# STM32H730_PINOUT.net
KiCad netlist of a schematic drawn in Altium Designer
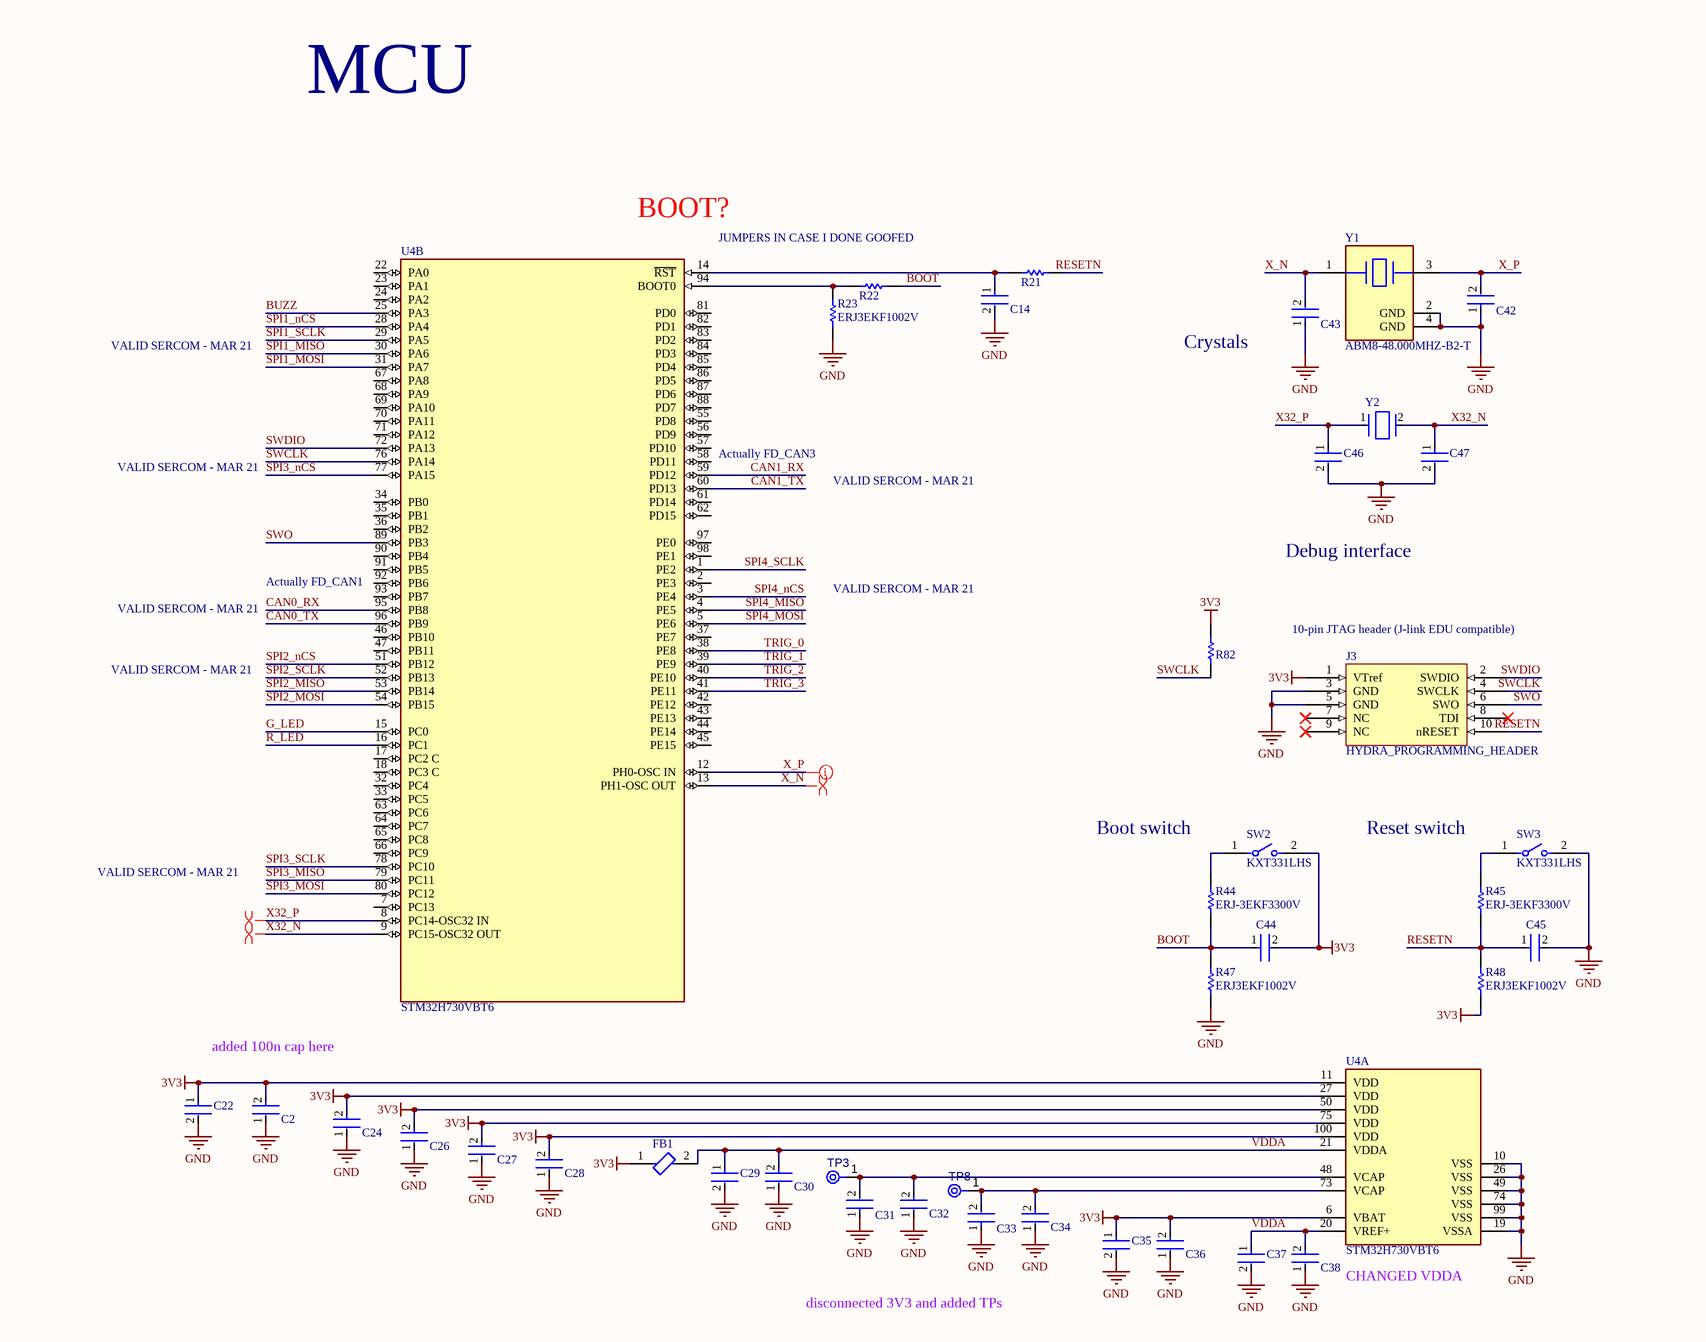
[diagram p0: STM32H730_PINOUT.SchDoc, top left]
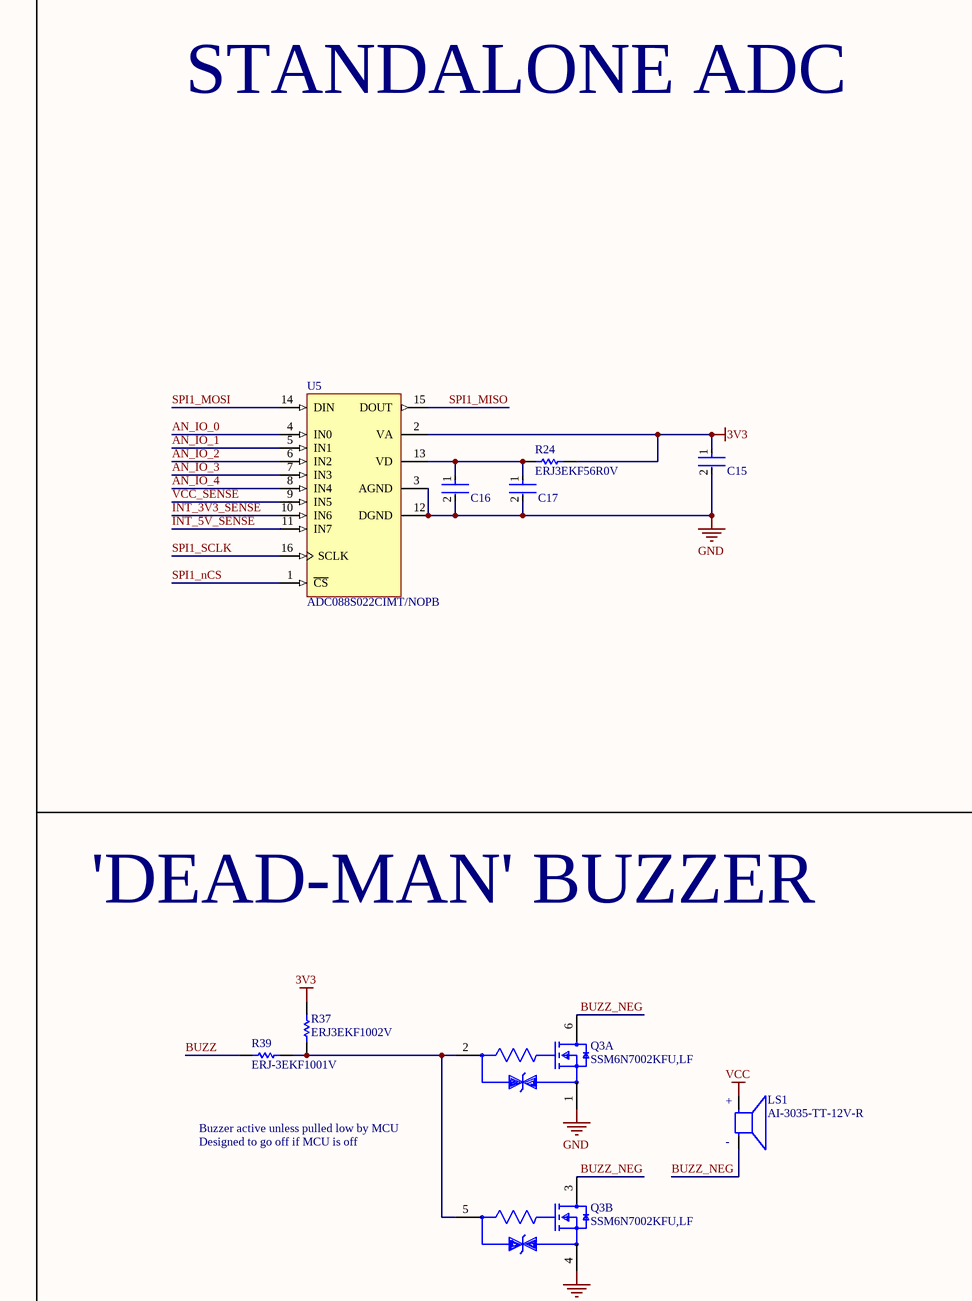
[diagram p1: STM32H730_PINOUT.SchDoc, top middle]
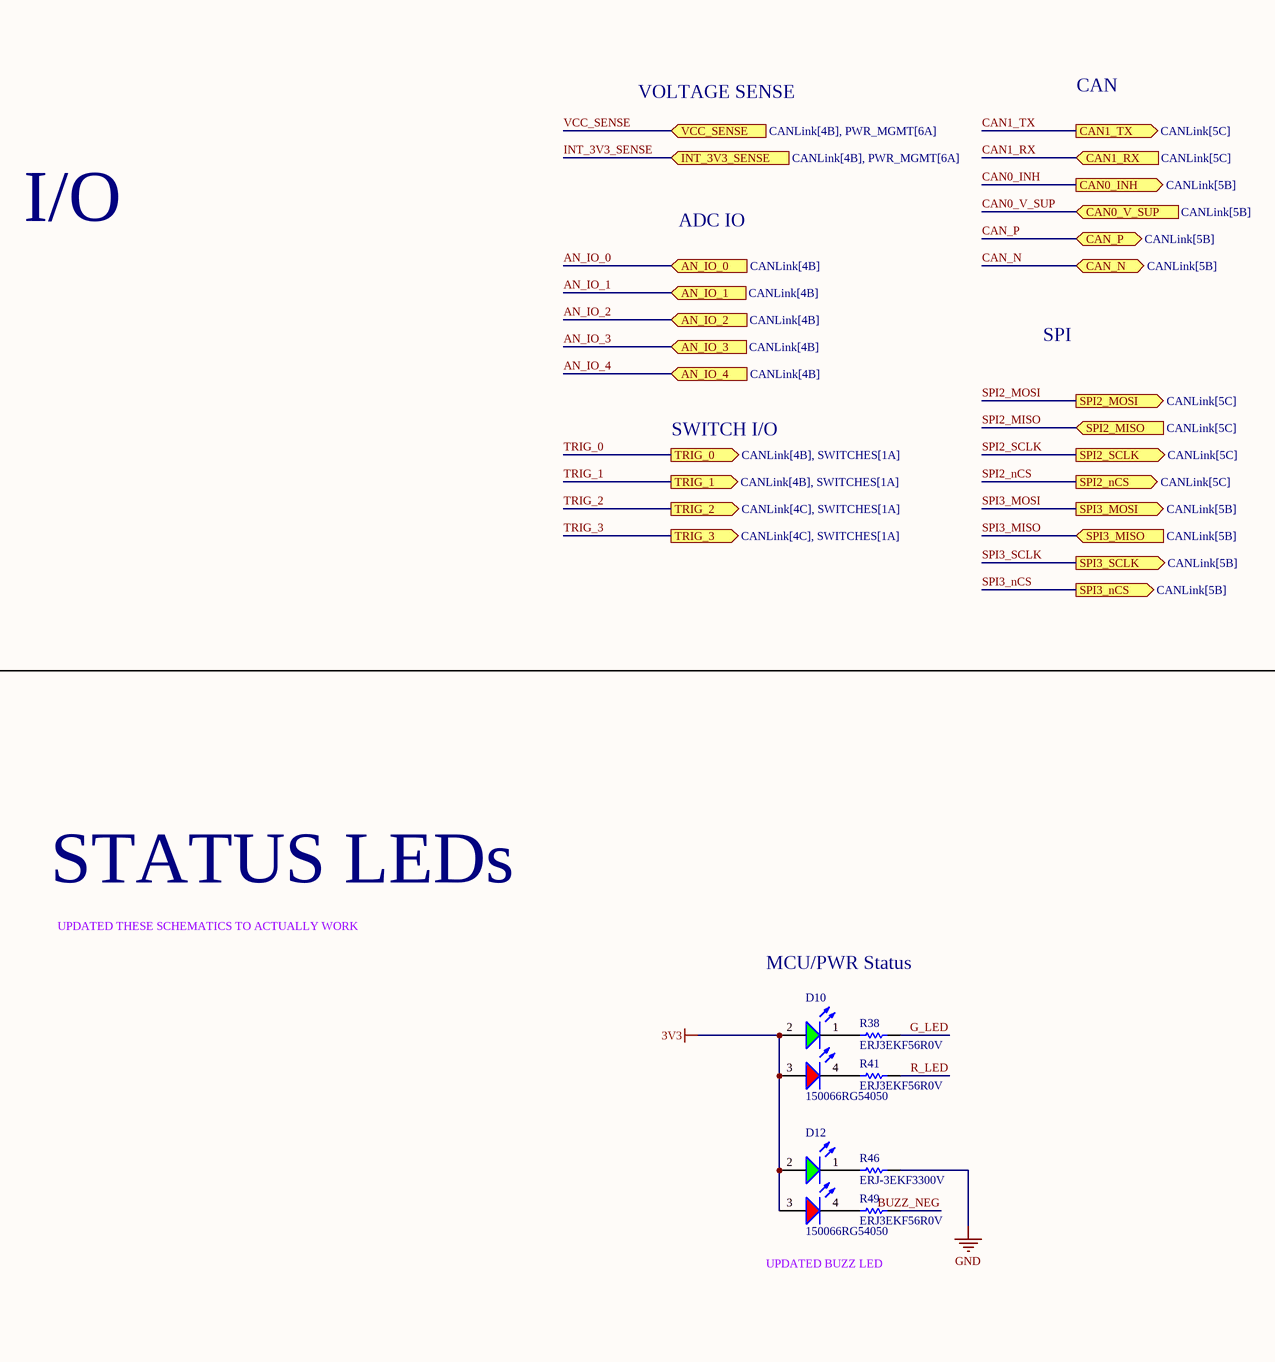
[diagram p2: STM32H730_PINOUT.SchDoc, top right]
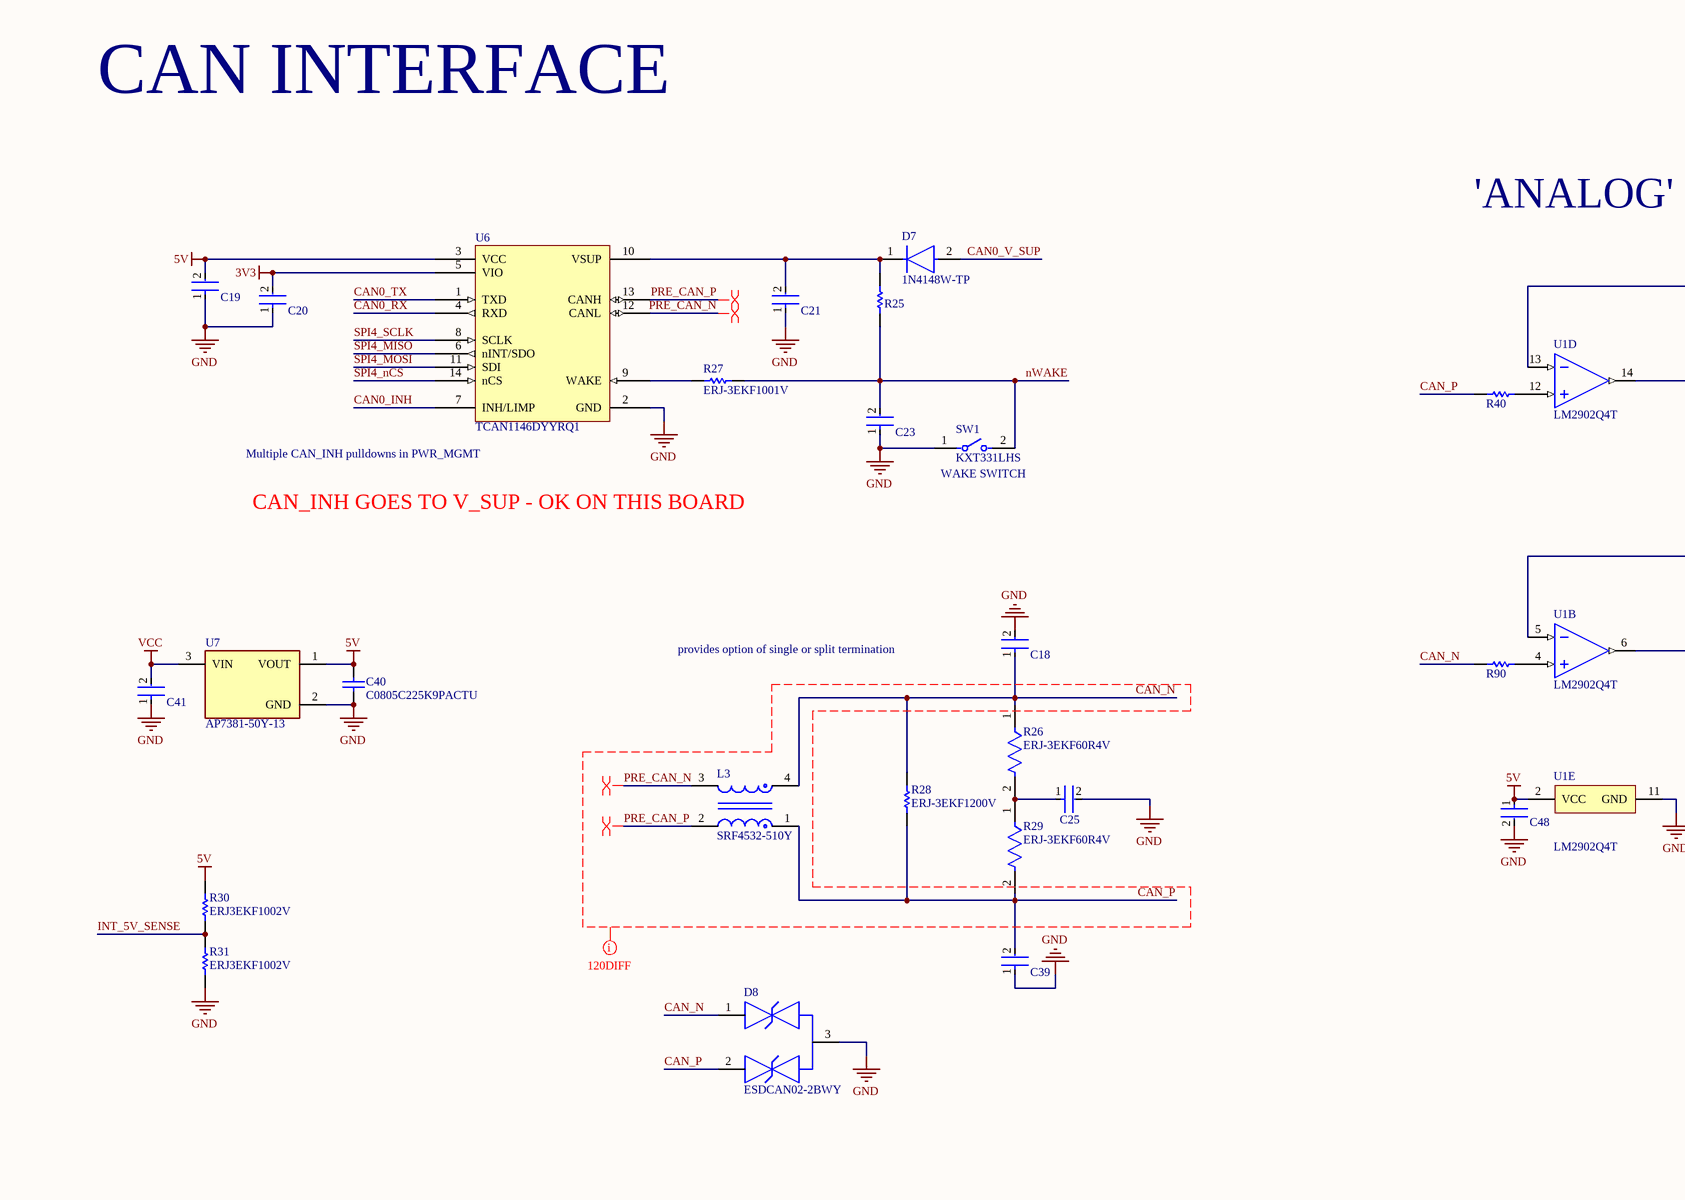
[diagram p3: STM32H730_PINOUT.SchDoc, bottom left]
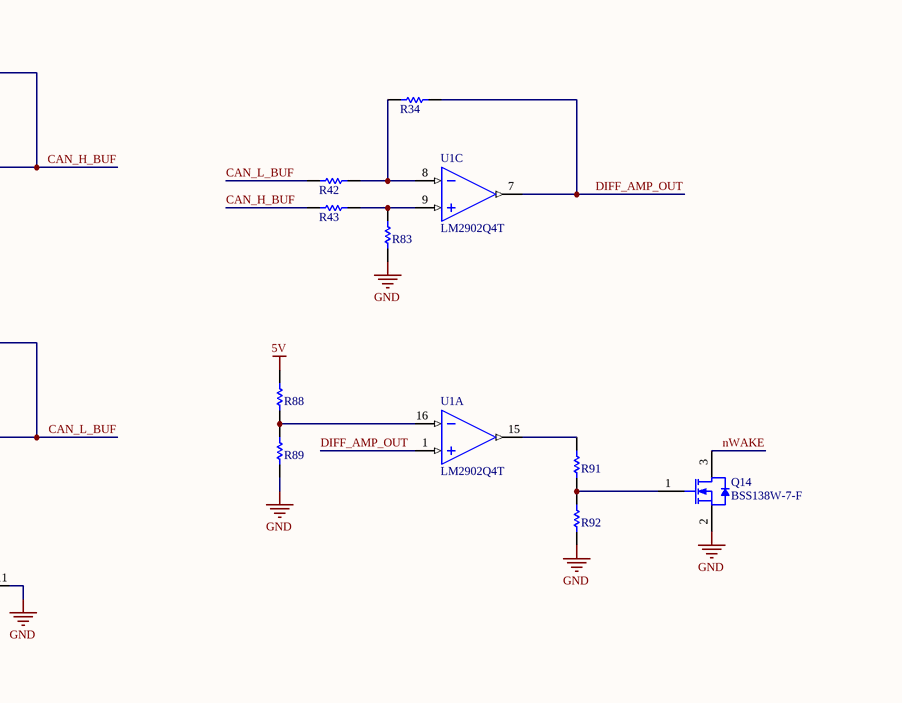
[diagram p4: STM32H730_PINOUT.SchDoc, bottom middle]
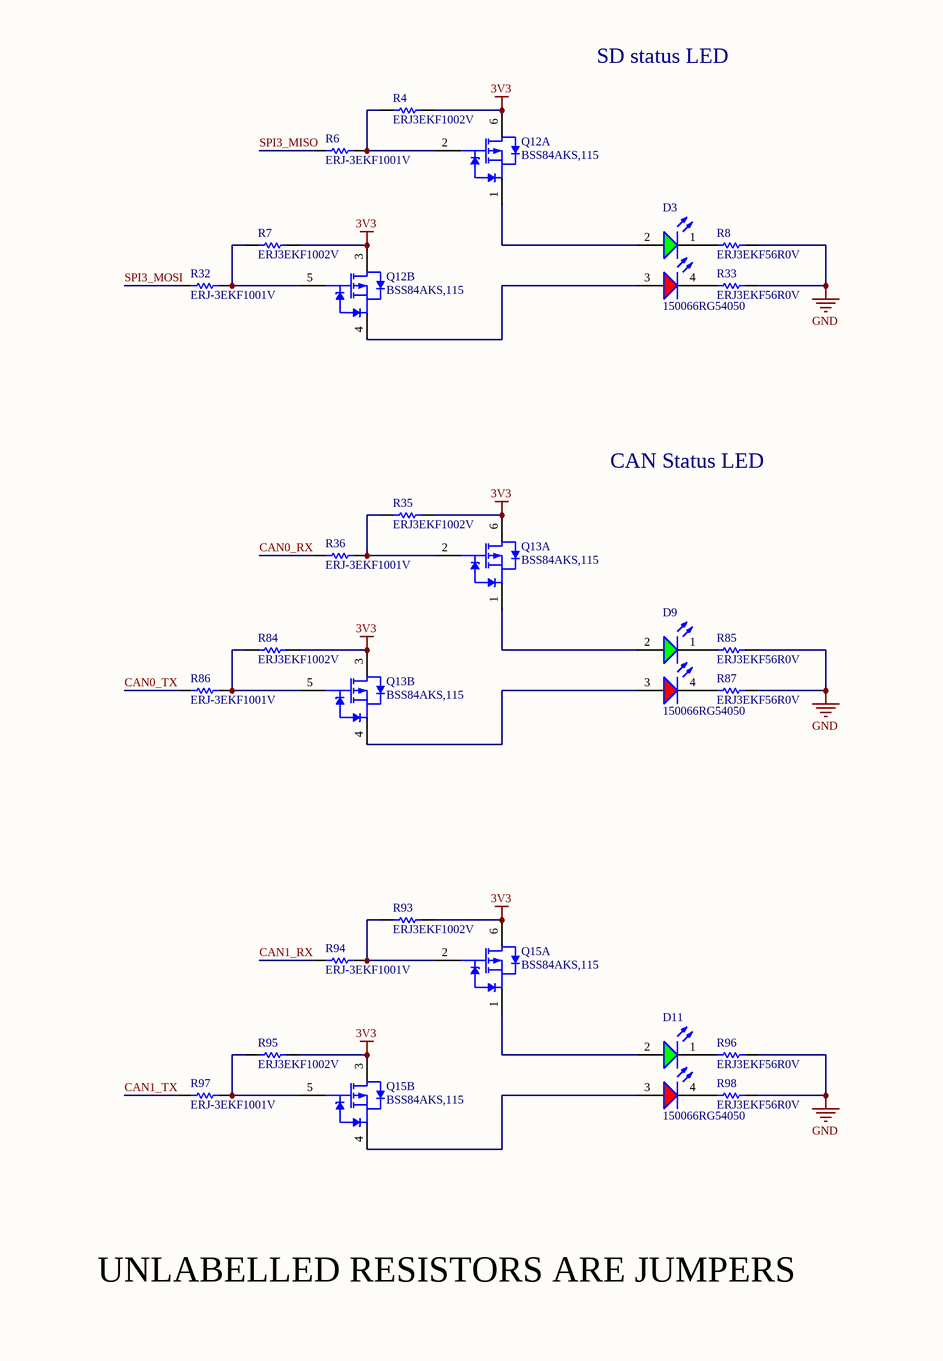
[diagram p5: STM32H730_PINOUT.SchDoc, bottom right]

(export (version "E")
  (design (tool "Eeschema 10.0.6"))
  (components
    (comp (ref "C2")
      (value "GRM155R71C104KA88D")
      (footprint "FP-GRM15-MFG")
      (description "CAP CER 0.1UF 16V X7R 0402")
      (fields
        (field (name "TOLERANCE") "10%")
        (field (name "OCTOPART") "https://octopart.com/grm155r71c104ka88d-murata-196880")
      )
      (libsource (lib "Altium Content Vault") (part "236180d848d6139a670b325ea6854c9"))
    )
    (comp (ref "C14")
      (value "C0402C104K8PACTU")
      (footprint "FP-C0402-BB-MFG")
      (description "CAP CER 0.1UF 10V X5R 0402")
      (fields (field (name "MANUFACTURER") "Kemet") (field (name "TOLERANCE") "0.1"))
      (libsource (lib "Altium Content Vault") (part "b4654b650e69147ec39a6b967a45e02"))
    )
    (comp (ref "C15")
      (value "C0402C104K8PACTU")
      (footprint "FP-C0402-BB-MFG")
      (description "CAP CER 0.1UF 10V X5R 0402")
      (fields (field (name "MANUFACTURER") "Kemet") (field (name "TOLERANCE") "0.1"))
      (libsource (lib "Altium Content Vault") (part "b4654b650e69147ec39a6b967a45e02"))
    )
    (comp (ref "C16")
      (value "C0402C104K8PACTU")
      (footprint "FP-C0402-BB-MFG")
      (description "CAP CER 0.1UF 10V X5R 0402")
      (fields (field (name "MANUFACTURER") "Kemet") (field (name "TOLERANCE") "0.1"))
      (libsource (lib "Altium Content Vault") (part "b4654b650e69147ec39a6b967a45e02"))
    )
    (comp (ref "C17")
      (value "C0402C104K8PACTU")
      (footprint "FP-C0402-BB-MFG")
      (description "CAP CER 0.1UF 10V X5R 0402")
      (fields (field (name "MANUFACTURER") "Kemet") (field (name "TOLERANCE") "0.1"))
      (libsource (lib "Altium Content Vault") (part "b4654b650e69147ec39a6b967a45e02"))
    )
    (comp (ref "C18")
      (value "C0402C104K8PACTU")
      (footprint "FP-C0402-BB-MFG")
      (description "CAP CER 0.1UF 10V X5R 0402")
      (fields (field (name "MANUFACTURER") "Kemet") (field (name "TOLERANCE") "0.1"))
      (libsource (lib "Altium Content Vault") (part "b4654b650e69147ec39a6b967a45e02"))
    )
    (comp (ref "C19")
      (value "C0402C104K8PACTU")
      (footprint "FP-C0402-BB-MFG")
      (description "CAP CER 0.1UF 10V X5R 0402")
      (fields (field (name "MANUFACTURER") "Kemet") (field (name "TOLERANCE") "0.1"))
      (libsource (lib "Altium Content Vault") (part "b4654b650e69147ec39a6b967a45e02"))
    )
    (comp (ref "C20")
      (value "C0402C104K8PACTU")
      (footprint "FP-C0402-BB-MFG")
      (description "CAP CER 0.1UF 10V X5R 0402")
      (fields (field (name "MANUFACTURER") "Kemet") (field (name "TOLERANCE") "0.1"))
      (libsource (lib "Altium Content Vault") (part "b4654b650e69147ec39a6b967a45e02"))
    )
    (comp (ref "C21")
      (value "C0402C104K8PACTU")
      (footprint "FP-C0402-BB-MFG")
      (description "CAP CER 0.1UF 10V X5R 0402")
      (fields (field (name "MANUFACTURER") "Kemet") (field (name "TOLERANCE") "0.1"))
      (libsource (lib "Altium Content Vault") (part "b4654b650e69147ec39a6b967a45e02"))
    )
    (comp (ref "C22")
      (value "C1005X5R1A475K050BC")
      (footprint "FP-C1005-050-0_15-MFG")
      (description "CAP CER 4.7UF 10V X5R 0402")
      (fields (field (name "TOLERANCE") "10%"))
      (libsource (lib "Altium Content Vault") (part "b4654b650e69147ec39a6b967a45e02"))
    )
    (comp (ref "C23")
      (value "C0402C104K8PACTU")
      (footprint "FP-C0402-BB-MFG")
      (description "CAP CER 0.1UF 10V X5R 0402")
      (fields (field (name "MANUFACTURER") "Kemet") (field (name "TOLERANCE") "0.1"))
      (libsource (lib "Altium Content Vault") (part "b4654b650e69147ec39a6b967a45e02"))
    )
    (comp (ref "C24")
      (value "GRM155R71C104KA88D")
      (footprint "FP-GRM15-MFG")
      (description "CAP CER 0.1UF 16V X7R 0402")
      (fields
        (field (name "TOLERANCE") "10%")
        (field (name "OCTOPART") "https://octopart.com/grm155r71c104ka88d-murata-196880")
      )
      (libsource (lib "Altium Content Vault") (part "236180d848d6139a670b325ea6854c9"))
    )
    (comp (ref "C25")
      (value "C0402C104K8PACTU")
      (footprint "FP-C0402-BB-MFG")
      (description "CAP CER 0.1UF 10V X5R 0402")
      (fields (field (name "MANUFACTURER") "Kemet") (field (name "TOLERANCE") "0.1"))
      (libsource (lib "Altium Content Vault") (part "b4654b650e69147ec39a6b967a45e02"))
    )
    (comp (ref "C26")
      (value "GRM155R71C104KA88D")
      (footprint "FP-GRM15-MFG")
      (description "CAP CER 0.1UF 16V X7R 0402")
      (fields
        (field (name "TOLERANCE") "10%")
        (field (name "OCTOPART") "https://octopart.com/grm155r71c104ka88d-murata-196880")
      )
      (libsource (lib "Altium Content Vault") (part "236180d848d6139a670b325ea6854c9"))
    )
    (comp (ref "C27")
      (value "GRM155R71C104KA88D")
      (footprint "FP-GRM15-MFG")
      (description "CAP CER 0.1UF 16V X7R 0402")
      (fields
        (field (name "TOLERANCE") "10%")
        (field (name "OCTOPART") "https://octopart.com/grm155r71c104ka88d-murata-196880")
      )
      (libsource (lib "Altium Content Vault") (part "236180d848d6139a670b325ea6854c9"))
    )
    (comp (ref "C28")
      (value "GRM155R71C104KA88D")
      (footprint "FP-GRM15-MFG")
      (description "CAP CER 0.1UF 16V X7R 0402")
      (fields
        (field (name "TOLERANCE") "10%")
        (field (name "OCTOPART") "https://octopart.com/grm155r71c104ka88d-murata-196880")
      )
      (libsource (lib "Altium Content Vault") (part "236180d848d6139a670b325ea6854c9"))
    )
    (comp (ref "C29")
      (value "EMK105BJ105KV-F")
      (footprint "FP-0402-L_1_0_0_05-W_0_5-IPC_A")
      (description "None")
      (fields (field (name "TOLERANCE") "10%"))
      (libsource (lib "Altium Content Vault") (part "b4654b650e69147ec39a6b967a45e02"))
    )
    (comp (ref "C30")
      (value "GRM155R71C104KA88D")
      (footprint "FP-GRM15-MFG")
      (description "CAP CER 0.1UF 16V X7R 0402")
      (fields
        (field (name "TOLERANCE") "10%")
        (field (name "OCTOPART") "https://octopart.com/grm155r71c104ka88d-murata-196880")
      )
      (libsource (lib "Altium Content Vault") (part "236180d848d6139a670b325ea6854c9"))
    )
    (comp (ref "C31")
      (value "C1005X7S1A225K050BC")
      (footprint "FP-C1005-050-0_15-0_1-MFG")
      (description "CAP CER 2.2UF 10V X7S 0402")
      (fields (field (name "TOLERANCE") "10%"))
      (libsource (lib "Altium Content Vault") (part "b4654b650e69147ec39a6b967a45e02"))
    )
    (comp (ref "C32")
      (value "GRM155R71C104KA88D")
      (footprint "FP-GRM15-MFG")
      (description "CAP CER 0.1UF 16V X7R 0402")
      (fields
        (field (name "TOLERANCE") "10%")
        (field (name "OCTOPART") "https://octopart.com/grm155r71c104ka88d-murata-196880")
      )
      (libsource (lib "Altium Content Vault") (part "236180d848d6139a670b325ea6854c9"))
    )
    (comp (ref "C33")
      (value "C1005X7S1A225K050BC")
      (footprint "FP-C1005-050-0_15-0_1-MFG")
      (description "CAP CER 2.2UF 10V X7S 0402")
      (fields (field (name "TOLERANCE") "10%"))
      (libsource (lib "Altium Content Vault") (part "b4654b650e69147ec39a6b967a45e02"))
    )
    (comp (ref "C34")
      (value "GRM155R71C104KA88D")
      (footprint "FP-GRM15-MFG")
      (description "CAP CER 0.1UF 16V X7R 0402")
      (fields
        (field (name "TOLERANCE") "10%")
        (field (name "OCTOPART") "https://octopart.com/grm155r71c104ka88d-murata-196880")
      )
      (libsource (lib "Altium Content Vault") (part "236180d848d6139a670b325ea6854c9"))
    )
    (comp (ref "C35")
      (value "EMK105BJ105KV-F")
      (footprint "FP-0402-L_1_0_0_05-W_0_5-IPC_A")
      (description "None")
      (fields (field (name "TOLERANCE") "10%"))
      (libsource (lib "Altium Content Vault") (part "b4654b650e69147ec39a6b967a45e02"))
    )
    (comp (ref "C36")
      (value "GRM155R71C104KA88D")
      (footprint "FP-GRM15-MFG")
      (description "CAP CER 0.1UF 16V X7R 0402")
      (fields
        (field (name "TOLERANCE") "10%")
        (field (name "OCTOPART") "https://octopart.com/grm155r71c104ka88d-murata-196880")
      )
      (libsource (lib "Altium Content Vault") (part "236180d848d6139a670b325ea6854c9"))
    )
    (comp (ref "C37")
      (value "EMK105BJ105KV-F")
      (footprint "FP-0402-L_1_0_0_05-W_0_5-IPC_A")
      (description "None")
      (fields (field (name "TOLERANCE") "10%"))
      (libsource (lib "Altium Content Vault") (part "b4654b650e69147ec39a6b967a45e02"))
    )
    (comp (ref "C38")
      (value "GRM155R71C104KA88D")
      (footprint "FP-GRM15-MFG")
      (description "CAP CER 0.1UF 16V X7R 0402")
      (fields
        (field (name "TOLERANCE") "10%")
        (field (name "OCTOPART") "https://octopart.com/grm155r71c104ka88d-murata-196880")
      )
      (libsource (lib "Altium Content Vault") (part "236180d848d6139a670b325ea6854c9"))
    )
    (comp (ref "C39")
      (value "C0402C104K8PACTU")
      (footprint "FP-C0402-BB-MFG")
      (description "CAP CER 0.1UF 10V X5R 0402")
      (fields (field (name "MANUFACTURER") "Kemet") (field (name "TOLERANCE") "0.1"))
      (libsource (lib "Altium Content Vault") (part "b4654b650e69147ec39a6b967a45e02"))
    )
    (comp (ref "C40")
      (value "C0805C225K9PACTU")
      (footprint "CAPC2013X145X50ML20T25")
      (fields (field (name "MANUFACTURER") "Kemet"))
      (libsource (lib "Altium Content Vault") (part "CAP"))
    )
    (comp (ref "C41")
      (value "C0402C104K8PACTU")
      (footprint "FP-C0402-BB-MFG")
      (description "CAP CER 0.1UF 10V X5R 0402")
      (fields (field (name "MANUFACTURER") "Kemet") (field (name "TOLERANCE") "0.1"))
      (libsource (lib "Altium Content Vault") (part "b4654b650e69147ec39a6b967a45e02"))
    )
    (comp (ref "C42")
      (value "08051A6R8CAT2A")
      (footprint "FP-0805-L_2_01_0_2-W_1_25-MFG")
      (description "General Purpose Ceramic Capacitor, 0805, 6.8pF, 0.25pF, C0G, 30ppm/°C, 100V")
      (fields (field (name "VOLTAGE") "100V") (field (name "TOLERANCE") "5%"))
      (libsource (lib "Altium Content Vault") (part "02cd4be3c70576c341d710602a673aa"))
    )
    (comp (ref "C43")
      (value "08051A6R8CAT2A")
      (footprint "FP-0805-L_2_01_0_2-W_1_25-MFG")
      (description "General Purpose Ceramic Capacitor, 0805, 6.8pF, 0.25pF, C0G, 30ppm/°C, 100V")
      (fields (field (name "VOLTAGE") "100V") (field (name "TOLERANCE") "5%"))
      (libsource (lib "Altium Content Vault") (part "02cd4be3c70576c341d710602a673aa"))
    )
    (comp (ref "C44")
      (value "C0402C104K8PACTU")
      (footprint "FP-C0402-BB-MFG")
      (description "CAP CER 0.1UF 10V X5R 0402")
      (fields (field (name "MANUFACTURER") "Kemet") (field (name "TOLERANCE") "0.1"))
      (libsource (lib "Altium Content Vault") (part "b4654b650e69147ec39a6b967a45e02"))
    )
    (comp (ref "C45")
      (value "C0402C104K8PACTU")
      (footprint "FP-C0402-BB-MFG")
      (description "CAP CER 0.1UF 10V X5R 0402")
      (fields (field (name "MANUFACTURER") "Kemet") (field (name "TOLERANCE") "0.1"))
      (libsource (lib "Altium Content Vault") (part "b4654b650e69147ec39a6b967a45e02"))
    )
    (comp (ref "C46")
      (value "C0805C180J5GACTU")
      (footprint "FP-C0805C-DN-MFG")
      (description "CAP CER 18PF 50V C0G/NP0 0805")
      (fields
        (field (name "OCTOPART") "https://octopart.com/c0805c180j5gactu-kemet-144810")
        (field (name "TOLERANCE") "0.05")
      )
      (libsource (lib "Altium Content Vault") (part "b4654b650e69147ec39a6b967a45e02"))
    )
    (comp (ref "C47")
      (value "C0805C180J5GACTU")
      (footprint "FP-C0805C-DN-MFG")
      (description "CAP CER 18PF 50V C0G/NP0 0805")
      (fields
        (field (name "OCTOPART") "https://octopart.com/c0805c180j5gactu-kemet-144810")
        (field (name "TOLERANCE") "0.05")
      )
      (libsource (lib "Altium Content Vault") (part "b4654b650e69147ec39a6b967a45e02"))
    )
    (comp (ref "C48")
      (value "C0402C104K8PACTU")
      (footprint "FP-C0402-BB-MFG")
      (description "CAP CER 0.1UF 10V X5R 0402")
      (fields (field (name "MANUFACTURER") "Kemet") (field (name "TOLERANCE") "0.1"))
      (libsource (lib "Altium Content Vault") (part "b4654b650e69147ec39a6b967a45e02"))
    )
    (comp (ref "D3")
      (value "150066RG54050")
      (footprint "WL-SBCD_0606")
      (description "Led, Red/Grn, 180Mcd/230Mcd, 624Nm/525Nm Rohs Compliant: Yes")
      (libsource (lib "uORocketry Hardware") (part "WL-SBCD_0606_Red & Green"))
    )
    (comp (ref "D7")
      (value "1N4148W-TP")
      (footprint "FP-SOD-123-IPC_A")
      (description "DIODE GEN PURP 100V 150MA SOD123")
      (libsource (lib "Altium Content Vault") (part "d7152d700b627762746794eb795d46e"))
    )
    (comp (ref "D8")
      (value "ESDCAN02-2BWY")
      (footprint "FP-SOT323-3L-MFG")
      (description "TVS DIODE 26.5V 44V SOT323-3")
      (fields
        (field (name "MANUFACTURER") "STMicroelectronics")
        (field (name "OCTOPART") "https://octopart.com/esdcan02-2bwy-stmicroelectronics-58631133")
      )
      (libsource (lib "Altium Content Vault") (part "0b9019fb5e52ed66df21ec1535be59d"))
    )
    (comp (ref "D9")
      (value "150066RG54050")
      (footprint "WL-SBCD_0606")
      (description "Led, Red/Grn, 180Mcd/230Mcd, 624Nm/525Nm Rohs Compliant: Yes")
      (libsource (lib "uORocketry Hardware") (part "WL-SBCD_0606_Red & Green"))
    )
    (comp (ref "D10")
      (value "150066RG54050")
      (footprint "WL-SBCD_0606")
      (description "Led, Red/Grn, 180Mcd/230Mcd, 624Nm/525Nm Rohs Compliant: Yes")
      (libsource (lib "uORocketry Hardware") (part "WL-SBCD_0606_Red & Green"))
    )
    (comp (ref "D11")
      (value "150066RG54050")
      (footprint "WL-SBCD_0606")
      (description "Led, Red/Grn, 180Mcd/230Mcd, 624Nm/525Nm Rohs Compliant: Yes")
      (libsource (lib "uORocketry Hardware") (part "WL-SBCD_0606_Red & Green"))
    )
    (comp (ref "D12")
      (value "150066RG54050")
      (footprint "WL-SBCD_0606")
      (description "Led, Red/Grn, 180Mcd/230Mcd, 624Nm/525Nm Rohs Compliant: Yes")
      (libsource (lib "uORocketry Hardware") (part "WL-SBCD_0606_Red & Green"))
    )
    (comp (ref "FB1")
      (value "BLM15PX601SN1D")
      (footprint "FP-BLM15-0_05-MFG")
      (description "Chip Ferrite Bead, 0402, 600Ω @ 100MHz, 0.23Ω, 25%, 900mA")
      (fields (field (name "TOLERANCE") "25%"))
      (libsource (lib "Altium Content Vault") (part "5f30dd21d616792df468990f7003faa"))
    )
    (comp (ref "J3")
      (value "HYDRA_PROGRAMMING_HEADER")
      (footprint "3220-10-0300-00-Footprint-1")
      (description "CONN HEADER SMD 10POS 1.27MM (specifically compatible with J-Link EDU cable) PN: 3220-10-0300-00")
      (libsource (lib "uORocketry Hardware") (part "3220-10-0300-00-Symbol-1"))
    )
    (comp (ref "L3")
      (value "SRF4532-510Y")
      (footprint "FP-SRF4532-MFG")
      (description "CMC 51UH 200MA 2LN 2KOHM SMD")
      (fields (field (name "TOLERANCE") "50%"))
      (libsource (lib "Altium Content Vault") (part "aca3f6a10b859f211cca95010157f3b"))
    )
    (comp (ref "LS1")
      (value "AI-3035-TT-12V-R")
      (footprint "AI-3035-TT-12V-R-Footprint-1")
      (description "Audio Indicator 12V 12mA 110dBA 3.5KHz Resonant Frequency Thru-Hole")
      (libsource (lib "uORocketry Hardware") (part "AI-3035-TT-12V-R"))
    )
    (comp (ref "Q3")
      (value "SSM6N7002KFU,LF")
      (footprint "FP-SSOP6-P-0_65A-MFG")
      (description "MOSFET 2N-CH 60V 0.3A")
      (libsource (lib "Altium Content Vault") (part "088aa6ac103fdeebe0d1c52ece6b7b9"))
    )
    (comp (ref "Q12")
      (value "BSS84AKS,115")
      (footprint "NXP-SOT363_L")
      (description "Dual P-Channel Trench MOSFET, -50 V, -0.16 A, -55 to 150 degC, 6-Pin SOT363, Tape and Reel")
      (fields (field (name "MANUFACTURER") "NXP Semiconductors"))
      (libsource (lib "Altium Content Vault") (part "NXP-PPMOS-SGDSGD-6_A"))
    )
    (comp (ref "Q13")
      (value "BSS84AKS,115")
      (footprint "NXP-SOT363_L")
      (description "Dual P-Channel Trench MOSFET, -50 V, -0.16 A, -55 to 150 degC, 6-Pin SOT363, Tape and Reel")
      (fields (field (name "MANUFACTURER") "NXP Semiconductors"))
      (libsource (lib "Altium Content Vault") (part "NXP-PPMOS-SGDSGD-6_A"))
    )
    (comp (ref "Q14")
      (value "BSS138W-7-F")
      (footprint "DIOD-SOT323-3_V")
      (fields (field (name "MANUFACTURER") "DiodesIncorporated"))
      (libsource (lib "Altium Content Vault") (part "NEMOS-GSD-3"))
    )
    (comp (ref "Q15")
      (value "BSS84AKS,115")
      (footprint "NXP-SOT363_L")
      (description "Dual P-Channel Trench MOSFET, -50 V, -0.16 A, -55 to 150 degC, 6-Pin SOT363, Tape and Reel")
      (fields (field (name "MANUFACTURER") "NXP Semiconductors"))
      (libsource (lib "Altium Content Vault") (part "NXP-PPMOS-SGDSGD-6_A"))
    )
    (comp (ref "R4")
      (value "ERJ3EKF1002V")
      (footprint "RESC1609X55X30LL15T15")
      (description "Chip Resistor, 10 KOhm, +/- 1%, 0.1 W, -55 to 155 degC, 0603 (1608 Metric), RoHS, Tape and Reel")
      (fields (field (name "TOLERANCE") "1%") (field (name "MANUFACTURER") "Panasonic"))
      (libsource (lib "Altium Content Vault") (part "RES-2"))
    )
    (comp (ref "R6")
      (value "ERJ-3EKF1001V")
      (footprint "RESC1608X55X30LL15T15")
      (fields (field (name "MANUFACTURER") "Panasonic"))
      (libsource (lib "Altium Content Vault") (part "RES"))
    )
    (comp (ref "R7")
      (value "ERJ3EKF1002V")
      (footprint "RESC1609X55X30LL15T15")
      (description "Chip Resistor, 10 KOhm, +/- 1%, 0.1 W, -55 to 155 degC, 0603 (1608 Metric), RoHS, Tape and Reel")
      (fields (field (name "TOLERANCE") "1%") (field (name "MANUFACTURER") "Panasonic"))
      (libsource (lib "Altium Content Vault") (part "RES-2"))
    )
    (comp (ref "R8")
      (value "ERJ3EKF56R0V")
      (footprint "RESC1608X55X30NL15T15")
      (fields (field (name "MANUFACTURER") "Panasonic"))
      (libsource (lib "Altium Content Vault") (part "RES"))
    )
    (comp (ref "R21")
      (value "0402 JUMPER 0 OHM")
      (footprint "RESC1005X40X25NL05T05")
      (description "READ THE NAME")
      (libsource (lib "uORocketry Hardware") (part "RES"))
    )
    (comp (ref "R22")
      (value "0402 JUMPER 0 OHM")
      (footprint "RESC1005X40X25NL05T05")
      (description "READ THE NAME")
      (libsource (lib "uORocketry Hardware") (part "RES"))
    )
    (comp (ref "R23")
      (value "ERJ3EKF1002V")
      (footprint "RESC1609X55X30LL15T15")
      (description "Chip Resistor, 10 KOhm, +/- 1%, 0.1 W, -55 to 155 degC, 0603 (1608 Metric), RoHS, Tape and Reel")
      (fields (field (name "TOLERANCE") "1%") (field (name "MANUFACTURER") "Panasonic"))
      (libsource (lib "Altium Content Vault") (part "RES-2"))
    )
    (comp (ref "R24")
      (value "ERJ3EKF56R0V")
      (footprint "RESC1608X55X30NL15T15")
      (fields (field (name "MANUFACTURER") "Panasonic"))
      (libsource (lib "Altium Content Vault") (part "RES"))
    )
    (comp (ref "R25")
      (value "ERJ3EKF1002V")
      (footprint "RESC1609X55X30LL15T15")
      (description "Chip Resistor, 10 KOhm, +/- 1%, 0.1 W, -55 to 155 degC, 0603 (1608 Metric), RoHS, Tape and Reel")
      (fields (field (name "TOLERANCE") "1%") (field (name "MANUFACTURER") "Panasonic"))
      (libsource (lib "Altium Content Vault") (part "RES-2"))
    )
    (comp (ref "R26")
      (value "ERJ-3EKF60R4V")
      (footprint "FP-ERJ3EK-IPC_C")
      (description "RES SMD 60.4 OHM 1% 1/10W 0603")
      (fields (field (name "TOLERANCE") "1%"))
      (libsource (lib "Altium Content Vault") (part "1029c3af85768c4190bb7ad29bc67b5"))
    )
    (comp (ref "R27")
      (value "ERJ-3EKF1001V")
      (footprint "RESC1608X55X30LL15T15")
      (fields (field (name "MANUFACTURER") "Panasonic"))
      (libsource (lib "Altium Content Vault") (part "RES"))
    )
    (comp (ref "R28")
      (value "ERJ-3EKF1200V")
      (footprint "RESC1609X55X30ML15T15")
      (description "Chip Resistor, 120 Ohm, +/- 1%, 0.1 W, -55 to 155 degC, 0603 (1608 Metric), RoHS, Tape and Reel")
      (fields (field (name "TOLERANCE") "1%") (field (name "MANUFACTURER") "Panasonic"))
      (libsource (lib "Altium Content Vault") (part "RES-2"))
    )
    (comp (ref "R29")
      (value "ERJ-3EKF60R4V")
      (footprint "FP-ERJ3EK-IPC_C")
      (description "RES SMD 60.4 OHM 1% 1/10W 0603")
      (fields (field (name "TOLERANCE") "1%"))
      (libsource (lib "Altium Content Vault") (part "1029c3af85768c4190bb7ad29bc67b5"))
    )
    (comp (ref "R30")
      (value "ERJ3EKF1002V")
      (footprint "RESC1609X55X30LL15T15")
      (description "Chip Resistor, 10 KOhm, +/- 1%, 0.1 W, -55 to 155 degC, 0603 (1608 Metric), RoHS, Tape and Reel")
      (fields (field (name "TOLERANCE") "1%") (field (name "MANUFACTURER") "Panasonic"))
      (libsource (lib "Altium Content Vault") (part "RES-2"))
    )
    (comp (ref "R31")
      (value "ERJ3EKF1002V")
      (footprint "RESC1609X55X30LL15T15")
      (description "Chip Resistor, 10 KOhm, +/- 1%, 0.1 W, -55 to 155 degC, 0603 (1608 Metric), RoHS, Tape and Reel")
      (fields (field (name "TOLERANCE") "1%") (field (name "MANUFACTURER") "Panasonic"))
      (libsource (lib "Altium Content Vault") (part "RES-2"))
    )
    (comp (ref "R32")
      (value "ERJ-3EKF1001V")
      (footprint "RESC1608X55X30LL15T15")
      (fields (field (name "MANUFACTURER") "Panasonic"))
      (libsource (lib "Altium Content Vault") (part "RES"))
    )
    (comp (ref "R33")
      (value "ERJ3EKF56R0V")
      (footprint "RESC1608X55X30NL15T15")
      (fields (field (name "MANUFACTURER") "Panasonic"))
      (libsource (lib "Altium Content Vault") (part "RES"))
    )
    (comp (ref "R34")
      (value "ERJ3EKF1002V")
      (footprint "RESC1609X55X30LL15T15")
      (description "Chip Resistor, 10 KOhm, +/- 1%, 0.1 W, -55 to 155 degC, 0603 (1608 Metric), RoHS, Tape and Reel")
      (fields (field (name "TOLERANCE") "1%") (field (name "MANUFACTURER") "Panasonic"))
      (libsource (lib "Altium Content Vault") (part "RES-2"))
    )
    (comp (ref "R35")
      (value "ERJ3EKF1002V")
      (footprint "RESC1609X55X30LL15T15")
      (description "Chip Resistor, 10 KOhm, +/- 1%, 0.1 W, -55 to 155 degC, 0603 (1608 Metric), RoHS, Tape and Reel")
      (fields (field (name "TOLERANCE") "1%") (field (name "MANUFACTURER") "Panasonic"))
      (libsource (lib "Altium Content Vault") (part "RES-2"))
    )
    (comp (ref "R36")
      (value "ERJ-3EKF1001V")
      (footprint "RESC1608X55X30LL15T15")
      (fields (field (name "MANUFACTURER") "Panasonic"))
      (libsource (lib "Altium Content Vault") (part "RES"))
    )
    (comp (ref "R37")
      (value "ERJ3EKF1002V")
      (footprint "RESC1609X55X30LL15T15")
      (description "Chip Resistor, 10 KOhm, +/- 1%, 0.1 W, -55 to 155 degC, 0603 (1608 Metric), RoHS, Tape and Reel")
      (fields (field (name "TOLERANCE") "1%") (field (name "MANUFACTURER") "Panasonic"))
      (libsource (lib "Altium Content Vault") (part "RES-2"))
    )
    (comp (ref "R38")
      (value "ERJ3EKF56R0V")
      (footprint "RESC1608X55X30NL15T15")
      (fields (field (name "MANUFACTURER") "Panasonic"))
      (libsource (lib "Altium Content Vault") (part "RES"))
    )
    (comp (ref "R39")
      (value "ERJ-3EKF1001V")
      (footprint "RESC1608X55X30LL15T15")
      (fields (field (name "MANUFACTURER") "Panasonic"))
      (libsource (lib "Altium Content Vault") (part "RES"))
    )
    (comp (ref "R40")
      (value "ERJ3EKF1002V")
      (footprint "RESC1609X55X30LL15T15")
      (description "Chip Resistor, 10 KOhm, +/- 1%, 0.1 W, -55 to 155 degC, 0603 (1608 Metric), RoHS, Tape and Reel")
      (fields (field (name "TOLERANCE") "1%") (field (name "MANUFACTURER") "Panasonic"))
      (libsource (lib "Altium Content Vault") (part "RES-2"))
    )
    (comp (ref "R41")
      (value "ERJ3EKF56R0V")
      (footprint "RESC1608X55X30NL15T15")
      (fields (field (name "MANUFACTURER") "Panasonic"))
      (libsource (lib "Altium Content Vault") (part "RES"))
    )
    (comp (ref "R42")
      (value "ERJ3EKF1002V")
      (footprint "RESC1609X55X30LL15T15")
      (description "Chip Resistor, 10 KOhm, +/- 1%, 0.1 W, -55 to 155 degC, 0603 (1608 Metric), RoHS, Tape and Reel")
      (fields (field (name "TOLERANCE") "1%") (field (name "MANUFACTURER") "Panasonic"))
      (libsource (lib "Altium Content Vault") (part "RES-2"))
    )
    (comp (ref "R43")
      (value "ERJ3EKF1002V")
      (footprint "RESC1609X55X30LL15T15")
      (description "Chip Resistor, 10 KOhm, +/- 1%, 0.1 W, -55 to 155 degC, 0603 (1608 Metric), RoHS, Tape and Reel")
      (fields (field (name "TOLERANCE") "1%") (field (name "MANUFACTURER") "Panasonic"))
      (libsource (lib "Altium Content Vault") (part "RES-2"))
    )
    (comp (ref "R44")
      (value "ERJ-3EKF3300V")
      (footprint "RESC1608X55X30LL15T15")
      (description "Chip Resistor, 330 Ohm, +/- 1%, 0.1 W, -55 to 155 degC, 0603 (1608 Metric), RoHS, Tape and Reel")
      (libsource (lib "Altium Content Vault") (part "RES-2"))
    )
    (comp (ref "R45")
      (value "ERJ-3EKF3300V")
      (footprint "RESC1608X55X30LL15T15")
      (description "Chip Resistor, 330 Ohm, +/- 1%, 0.1 W, -55 to 155 degC, 0603 (1608 Metric), RoHS, Tape and Reel")
      (libsource (lib "Altium Content Vault") (part "RES-2"))
    )
    (comp (ref "R46")
      (value "ERJ-3EKF3300V")
      (footprint "RESC1608X55X30LL15T15")
      (description "Chip Resistor, 330 Ohm, +/- 1%, 0.1 W, -55 to 155 degC, 0603 (1608 Metric), RoHS, Tape and Reel")
      (libsource (lib "Altium Content Vault") (part "RES-2"))
    )
    (comp (ref "R47")
      (value "ERJ3EKF1002V")
      (footprint "RESC1609X55X30LL15T15")
      (description "Chip Resistor, 10 KOhm, +/- 1%, 0.1 W, -55 to 155 degC, 0603 (1608 Metric), RoHS, Tape and Reel")
      (fields (field (name "TOLERANCE") "1%") (field (name "MANUFACTURER") "Panasonic"))
      (libsource (lib "Altium Content Vault") (part "RES-2"))
    )
    (comp (ref "R48")
      (value "ERJ3EKF1002V")
      (footprint "RESC1609X55X30LL15T15")
      (description "Chip Resistor, 10 KOhm, +/- 1%, 0.1 W, -55 to 155 degC, 0603 (1608 Metric), RoHS, Tape and Reel")
      (fields (field (name "TOLERANCE") "1%") (field (name "MANUFACTURER") "Panasonic"))
      (libsource (lib "Altium Content Vault") (part "RES-2"))
    )
    (comp (ref "R49")
      (value "ERJ3EKF56R0V")
      (footprint "RESC1608X55X30NL15T15")
      (fields (field (name "MANUFACTURER") "Panasonic"))
      (libsource (lib "Altium Content Vault") (part "RES"))
    )
    (comp (ref "R82")
      (value "ERJ3EKF1002V")
      (footprint "RESC1609X55X30LL15T15")
      (description "Chip Resistor, 10 KOhm, +/- 1%, 0.1 W, -55 to 155 degC, 0603 (1608 Metric), RoHS, Tape and Reel")
      (fields (field (name "TOLERANCE") "1%") (field (name "MANUFACTURER") "Panasonic"))
      (libsource (lib "Altium Content Vault") (part "RES-2"))
    )
    (comp (ref "R83")
      (value "ERJ3EKF1002V")
      (footprint "RESC1609X55X30LL15T15")
      (description "Chip Resistor, 10 KOhm, +/- 1%, 0.1 W, -55 to 155 degC, 0603 (1608 Metric), RoHS, Tape and Reel")
      (fields (field (name "TOLERANCE") "1%") (field (name "MANUFACTURER") "Panasonic"))
      (libsource (lib "Altium Content Vault") (part "RES-2"))
    )
    (comp (ref "R84")
      (value "ERJ3EKF1002V")
      (footprint "RESC1609X55X30LL15T15")
      (description "Chip Resistor, 10 KOhm, +/- 1%, 0.1 W, -55 to 155 degC, 0603 (1608 Metric), RoHS, Tape and Reel")
      (fields (field (name "TOLERANCE") "1%") (field (name "MANUFACTURER") "Panasonic"))
      (libsource (lib "Altium Content Vault") (part "RES-2"))
    )
    (comp (ref "R85")
      (value "ERJ3EKF56R0V")
      (footprint "RESC1608X55X30NL15T15")
      (fields (field (name "MANUFACTURER") "Panasonic"))
      (libsource (lib "Altium Content Vault") (part "RES"))
    )
    (comp (ref "R86")
      (value "ERJ-3EKF1001V")
      (footprint "RESC1608X55X30LL15T15")
      (fields (field (name "MANUFACTURER") "Panasonic"))
      (libsource (lib "Altium Content Vault") (part "RES"))
    )
    (comp (ref "R87")
      (value "ERJ3EKF56R0V")
      (footprint "RESC1608X55X30NL15T15")
      (fields (field (name "MANUFACTURER") "Panasonic"))
      (libsource (lib "Altium Content Vault") (part "RES"))
    )
    (comp (ref "R88")
      (value "ERJ3EKF1002V")
      (footprint "RESC1609X55X30LL15T15")
      (description "Chip Resistor, 10 KOhm, +/- 1%, 0.1 W, -55 to 155 degC, 0603 (1608 Metric), RoHS, Tape and Reel")
      (fields (field (name "TOLERANCE") "1%") (field (name "MANUFACTURER") "Panasonic"))
      (libsource (lib "Altium Content Vault") (part "RES-2"))
    )
    (comp (ref "R89")
      (value "ERJ-3EKF1001V")
      (footprint "RESC1608X55X30LL15T15")
      (fields (field (name "MANUFACTURER") "Panasonic"))
      (libsource (lib "Altium Content Vault") (part "RES"))
    )
    (comp (ref "R90")
      (value "ERJ3EKF1002V")
      (footprint "RESC1609X55X30LL15T15")
      (description "Chip Resistor, 10 KOhm, +/- 1%, 0.1 W, -55 to 155 degC, 0603 (1608 Metric), RoHS, Tape and Reel")
      (fields (field (name "TOLERANCE") "1%") (field (name "MANUFACTURER") "Panasonic"))
      (libsource (lib "Altium Content Vault") (part "RES-2"))
    )
    (comp (ref "R91")
      (value "ERJ3EKF1002V")
      (footprint "RESC1609X55X30LL15T15")
      (description "Chip Resistor, 10 KOhm, +/- 1%, 0.1 W, -55 to 155 degC, 0603 (1608 Metric), RoHS, Tape and Reel")
      (fields (field (name "TOLERANCE") "1%") (field (name "MANUFACTURER") "Panasonic"))
      (libsource (lib "Altium Content Vault") (part "RES-2"))
    )
    (comp (ref "R92")
      (value "ERJ3EKF1002V")
      (footprint "RESC1609X55X30LL15T15")
      (description "Chip Resistor, 10 KOhm, +/- 1%, 0.1 W, -55 to 155 degC, 0603 (1608 Metric), RoHS, Tape and Reel")
      (fields (field (name "TOLERANCE") "1%") (field (name "MANUFACTURER") "Panasonic"))
      (libsource (lib "Altium Content Vault") (part "RES-2"))
    )
    (comp (ref "R93")
      (value "ERJ3EKF1002V")
      (footprint "RESC1609X55X30LL15T15")
      (description "Chip Resistor, 10 KOhm, +/- 1%, 0.1 W, -55 to 155 degC, 0603 (1608 Metric), RoHS, Tape and Reel")
      (fields (field (name "TOLERANCE") "1%") (field (name "MANUFACTURER") "Panasonic"))
      (libsource (lib "Altium Content Vault") (part "RES-2"))
    )
    (comp (ref "R94")
      (value "ERJ-3EKF1001V")
      (footprint "RESC1608X55X30LL15T15")
      (fields (field (name "MANUFACTURER") "Panasonic"))
      (libsource (lib "Altium Content Vault") (part "RES"))
    )
    (comp (ref "R95")
      (value "ERJ3EKF1002V")
      (footprint "RESC1609X55X30LL15T15")
      (description "Chip Resistor, 10 KOhm, +/- 1%, 0.1 W, -55 to 155 degC, 0603 (1608 Metric), RoHS, Tape and Reel")
      (fields (field (name "TOLERANCE") "1%") (field (name "MANUFACTURER") "Panasonic"))
      (libsource (lib "Altium Content Vault") (part "RES-2"))
    )
    (comp (ref "R96")
      (value "ERJ3EKF56R0V")
      (footprint "RESC1608X55X30NL15T15")
      (fields (field (name "MANUFACTURER") "Panasonic"))
      (libsource (lib "Altium Content Vault") (part "RES"))
    )
    (comp (ref "R97")
      (value "ERJ-3EKF1001V")
      (footprint "RESC1608X55X30LL15T15")
      (fields (field (name "MANUFACTURER") "Panasonic"))
      (libsource (lib "Altium Content Vault") (part "RES"))
    )
    (comp (ref "R98")
      (value "ERJ3EKF56R0V")
      (footprint "RESC1608X55X30NL15T15")
      (fields (field (name "MANUFACTURER") "Panasonic"))
      (libsource (lib "Altium Content Vault") (part "RES"))
    )
    (comp (ref "SW1")
      (value "KXT331LHS")
      (footprint "FP-KXT331LHS-MFG")
      (description "SWITCH TACTILE SPST-NO 0.02A 15V")
      (libsource (lib "Altium Content Vault") (part "bb27bde45df87f1f469753f287ef5ae"))
    )
    (comp (ref "SW2")
      (value "KXT331LHS")
      (footprint "FP-KXT331LHS-MFG")
      (description "SWITCH TACTILE SPST-NO 0.02A 15V")
      (libsource (lib "Altium Content Vault") (part "bb27bde45df87f1f469753f287ef5ae"))
    )
    (comp (ref "SW3")
      (value "KXT331LHS")
      (footprint "FP-KXT331LHS-MFG")
      (description "SWITCH TACTILE SPST-NO 0.02A 15V")
      (libsource (lib "Altium Content Vault") (part "bb27bde45df87f1f469753f287ef5ae"))
    )
    (comp (ref "TP3")
      (value "TPAD6R")
      (footprint "TP06R")
      (description "0.6mm round")
      (libsource (lib "uORocketry Hardware") (part "CMP-001-0001-4"))
    )
    (comp (ref "TP8")
      (value "TPAD6R")
      (footprint "TP06R")
      (description "0.6mm round")
      (libsource (lib "uORocketry Hardware") (part "CMP-001-0001-4"))
    )
    (comp (ref "U1")
      (value "LM2902Q4T")
      (footprint "LM2902Q4T-Footprint-1")
      (description "LM2902 Series 30 V 1.3 MHz Low-Power Quad Operational Amplifier - QFN-16 (3x3)")
      (libsource (lib "uORocketry Hardware") (part "LM2902Q4T"))
    )
    (comp (ref "U4")
      (value "STM32H730VBT6")
      (footprint "FP-LQFP100-1L-IPC_C")
      (description "IC MCU 32BIT 128KB FLASH 100LQFP")
      (libsource (lib "Altium Content Vault") (part "44dc6501260a4d92b846760feb66c20"))
    )
    (comp (ref "U5")
      (value "ADC088S022CIMT/NOPB")
      (footprint "MTC16_L")
      (description "8-Channel, 50 kSPS to 200 kSPS, 8-Bit A/D Converter, 16-pin TSSOP, Pb-Free")
      (fields (field (name "MANUFACTURER") "National Semiconductor"))
      (libsource (lib "Altium Content Vault") (part "CON-ADC-ADC108S052CIMT"))
    )
    (comp (ref "U6")
      (value "TCAN1146DYYRQ1")
      (footprint "TCAN1146DYYRQ1-Footprint-1")
      (libsource (lib "uORocketry Hardware") (part "TCAN1146DYYRQ1"))
    )
    (comp (ref "U7")
      (value "AP7381-50Y-13")
      (footprint "FP-SOT89-MFG")
      (description "IC REG LINEAR 5V 150MA SOT89")
      (fields
        (field (name "MANUFACTURER") "Diodes Inc.")
        (field (name "OCTOPART") "https://octopart.com/ap7381-50y-13-diodes+inc.-87775116")
      )
      (libsource (lib "Altium Content Vault") (part "4c3da590f2d7b1882ad42f13e6d336b"))
    )
    (comp (ref "Y1")
      (value "ABM8-48.000MHZ-B2-T")
      (footprint "FP-ABM8-MFG")
      (description "Crystal 48MHz ±20ppm 18pF SMD-4 3.2mm x 2.5mm")
      (fields (field (name "TOLERANCE") "20ppm"))
      (libsource (lib "Altium Content Vault") (part "dfdb7f9a12507849fb681da9a70121c"))
    )
    (comp (ref "Y2")
      (value "ECS-.327-12.5-1210-TR")
      (footprint "FP-ECX-1210-MFG")
      (description "CRYSTAL 32.7680KHZ 12.5PF SMD")
      (fields
        (field (name "OCTOPART") "https://octopart.com/ecs-.327-12.5-1210-tr-ecs+international-81221340")
        (field (name "TOLERANCE") "20ppm")
      )
      (libsource (lib "Altium Content Vault") (part "99724985039315a44fd0d1401b84e49"))
    )
  )
  (nets
    (net (code "1") (name "/AN_IO_0") (class "Default")
      (node (ref "U5") (pin "4") (pinfunction "IN0_4") (pintype "input"))
    )
    (net (code "2") (name "/AN_IO_1") (class "Default")
      (node (ref "U5") (pin "5") (pinfunction "IN1_5") (pintype "input"))
    )
    (net (code "3") (name "/AN_IO_2") (class "Default")
      (node (ref "U5") (pin "6") (pinfunction "IN2_6") (pintype "input"))
    )
    (net (code "4") (name "/AN_IO_3") (class "Default")
      (node (ref "U5") (pin "7") (pinfunction "IN3_7") (pintype "input"))
    )
    (net (code "5") (name "/AN_IO_4") (class "Default")
      (node (ref "U5") (pin "8") (pinfunction "IN4_8") (pintype "input"))
    )
    (net (code "6") (name "/BOOT") (class "Default")
      (node (ref "C44") (pin "1") (pinfunction "1_1") (pintype "passive"))
      (node (ref "R22") (pin "2") (pinfunction "2_2") (pintype "passive"))
      (node (ref "R44") (pin "1") (pinfunction "1_1") (pintype "passive"))
      (node (ref "R47") (pin "2") (pinfunction "2_2") (pintype "passive"))
    )
    (net (code "7") (name "/BUZZ") (class "Default")
      (node (ref "R39") (pin "1") (pinfunction "1_1") (pintype "passive"))
      (node (ref "U4") (pin "25") (pinfunction "PA3_25") (pintype "bidirectional"))
    )
    (net (code "8") (name "/BUZZ_NEG") (class "Default")
      (node (ref "LS1") (pin "N") (pinfunction "N_N") (pintype "passive"))
      (node (ref "Q3") (pin "3") (pinfunction "Drain2_3") (pintype "passive"))
      (node (ref "Q3") (pin "6") (pinfunction "Drain1_6") (pintype "passive"))
      (node (ref "R49") (pin "1") (pinfunction "1_1") (pintype "passive"))
    )
    (net (code "9") (name "/CAN0_INH") (class "Default")
      (node (ref "U6") (pin "7") (pinfunction "INH/LIMP_7") (pintype "passive"))
    )
    (net (code "10") (name "/CAN0_RX") (class "Default")
      (node (ref "R36") (pin "1") (pinfunction "1_1") (pintype "passive"))
      (node (ref "U4") (pin "95") (pinfunction "PB8_95") (pintype "bidirectional"))
      (node (ref "U6") (pin "4") (pinfunction "RXD_4") (pintype "output"))
    )
    (net (code "11") (name "/CAN0_TX") (class "Default")
      (node (ref "R86") (pin "1") (pinfunction "1_1") (pintype "passive"))
      (node (ref "U4") (pin "96") (pinfunction "PB9_96") (pintype "bidirectional"))
      (node (ref "U6") (pin "1") (pinfunction "TXD_1") (pintype "input"))
    )
    (net (code "12") (name "/CAN0_V_SUP") (class "Default")
      (node (ref "D7") (pin "2") (pinfunction "A_2") (pintype "passive"))
    )
    (net (code "13") (name "/CAN1_RX") (class "Default")
      (node (ref "R94") (pin "1") (pinfunction "1_1") (pintype "passive"))
      (node (ref "U4") (pin "59") (pinfunction "PD12_59") (pintype "bidirectional"))
    )
    (net (code "14") (name "/CAN1_TX") (class "Default")
      (node (ref "R97") (pin "1") (pinfunction "1_1") (pintype "passive"))
      (node (ref "U4") (pin "60") (pinfunction "PD13_60") (pintype "bidirectional"))
    )
    (net (code "15") (name "/CAN_H_BUF") (class "Default")
      (node (ref "R43") (pin "1") (pinfunction "1_1") (pintype "passive"))
      (node (ref "U1") (pin "13") (pinfunction "4IN-_13") (pintype "input"))
      (node (ref "U1") (pin "14") (pinfunction "4OUT_14") (pintype "output"))
    )
    (net (code "16") (name "/CAN_L_BUF") (class "Default")
      (node (ref "R42") (pin "1") (pinfunction "1_1") (pintype "passive"))
      (node (ref "U1") (pin "5") (pinfunction "2IN-_5") (pintype "input"))
      (node (ref "U1") (pin "6") (pinfunction "2OUT_6") (pintype "output"))
    )
    (net (code "17") (name "/CAN_N") (class "Default")
      (node (ref "C18") (pin "1") (pinfunction "1_1") (pintype "passive"))
      (node (ref "D8") (pin "1") (pinfunction "1_1") (pintype "passive"))
      (node (ref "L3") (pin "4") (pinfunction "4_4") (pintype "passive"))
      (node (ref "R26") (pin "1") (pinfunction "1_1") (pintype "passive"))
      (node (ref "R28") (pin "1") (pinfunction "1_1") (pintype "passive"))
      (node (ref "R90") (pin "1") (pinfunction "1_1") (pintype "passive"))
    )
    (net (code "18") (name "/CAN_P") (class "Default")
      (node (ref "C39") (pin "2") (pinfunction "2_2") (pintype "passive"))
      (node (ref "D8") (pin "2") (pinfunction "2_2") (pintype "passive"))
      (node (ref "L3") (pin "1") (pinfunction "1_1") (pintype "passive"))
      (node (ref "R28") (pin "2") (pinfunction "2_2") (pintype "passive"))
      (node (ref "R29") (pin "2") (pinfunction "2_2") (pintype "passive"))
      (node (ref "R40") (pin "1") (pinfunction "1_1") (pintype "passive"))
    )
    (net (code "19") (name "/DIFF_AMP_OUT") (class "Default")
      (node (ref "R34") (pin "2") (pinfunction "2_2") (pintype "passive"))
      (node (ref "U1") (pin "1") (pinfunction "1IN+_1") (pintype "input"))
      (node (ref "U1") (pin "7") (pinfunction "3OUT_7") (pintype "output"))
    )
    (net (code "20") (name "/G_LED") (class "Default")
      (node (ref "R38") (pin "1") (pinfunction "1_1") (pintype "passive"))
      (node (ref "U4") (pin "15") (pinfunction "PC0_15") (pintype "bidirectional"))
    )
    (net (code "21") (name "/INT_3V3_SENSE") (class "Default")
      (node (ref "U5") (pin "10") (pinfunction "IN6_10") (pintype "input"))
    )
    (net (code "22") (name "/INT_5V_SENSE") (class "Default")
      (node (ref "R30") (pin "1") (pinfunction "1_1") (pintype "passive"))
      (node (ref "R31") (pin "1") (pinfunction "1_1") (pintype "passive"))
      (node (ref "U5") (pin "11") (pinfunction "IN7_11") (pintype "input"))
    )
    (net (code "23") (name "/PRE_CAN_N") (class "Default")
      (node (ref "L3") (pin "3") (pinfunction "3_3") (pintype "passive"))
      (node (ref "U6") (pin "12") (pinfunction "CANL_12") (pintype "bidirectional"))
    )
    (net (code "24") (name "/PRE_CAN_P") (class "Default")
      (node (ref "L3") (pin "2") (pinfunction "2_2") (pintype "passive"))
      (node (ref "U6") (pin "13") (pinfunction "CANH_13") (pintype "bidirectional"))
    )
    (net (code "25") (name "/RESETN") (class "Default")
      (node (ref "C45") (pin "1") (pinfunction "1_1") (pintype "passive"))
      (node (ref "J3") (pin "10") (pinfunction "nRESET_10") (pintype "input"))
      (node (ref "R21") (pin "2") (pinfunction "2_2") (pintype "passive"))
      (node (ref "R45") (pin "1") (pinfunction "1_1") (pintype "passive"))
      (node (ref "R48") (pin "2") (pinfunction "2_2") (pintype "passive"))
    )
    (net (code "26") (name "/R_LED") (class "Default")
      (node (ref "R41") (pin "1") (pinfunction "1_1") (pintype "passive"))
      (node (ref "U4") (pin "16") (pinfunction "PC1_16") (pintype "bidirectional"))
    )
    (net (code "27") (name "/SPI1_MISO") (class "Default")
      (node (ref "U4") (pin "30") (pinfunction "PA6_30") (pintype "bidirectional"))
      (node (ref "U5") (pin "15") (pinfunction "DOUT_15") (pintype "output"))
    )
    (net (code "28") (name "/SPI1_MOSI") (class "Default")
      (node (ref "U4") (pin "31") (pinfunction "PA7_31") (pintype "bidirectional"))
      (node (ref "U5") (pin "14") (pinfunction "DIN_14") (pintype "input"))
    )
    (net (code "29") (name "/SPI1_SCLK") (class "Default")
      (node (ref "U4") (pin "29") (pinfunction "PA5_29") (pintype "bidirectional"))
      (node (ref "U5") (pin "16") (pinfunction "SCLK_16") (pintype "input"))
    )
    (net (code "30") (name "/SPI1_nCS") (class "Default")
      (node (ref "U4") (pin "28") (pinfunction "PA4_28") (pintype "bidirectional"))
      (node (ref "U5") (pin "1") (pinfunction "~{CS}_1") (pintype "input"))
    )
    (net (code "31") (name "/SPI2_MISO") (class "Default")
      (node (ref "U4") (pin "53") (pinfunction "PB14_53") (pintype "bidirectional"))
    )
    (net (code "32") (name "/SPI2_MOSI") (class "Default")
      (node (ref "U4") (pin "54") (pinfunction "PB15_54") (pintype "bidirectional"))
    )
    (net (code "33") (name "/SPI2_SCLK") (class "Default")
      (node (ref "U4") (pin "52") (pinfunction "PB13_52") (pintype "bidirectional"))
    )
    (net (code "34") (name "/SPI2_nCS") (class "Default")
      (node (ref "U4") (pin "51") (pinfunction "PB12_51") (pintype "bidirectional"))
    )
    (net (code "35") (name "/SPI3_MISO") (class "Default")
      (node (ref "R6") (pin "1") (pinfunction "1_1") (pintype "passive"))
      (node (ref "U4") (pin "79") (pinfunction "PC11_79") (pintype "bidirectional"))
    )
    (net (code "36") (name "/SPI3_MOSI") (class "Default")
      (node (ref "R32") (pin "1") (pinfunction "1_1") (pintype "passive"))
      (node (ref "U4") (pin "80") (pinfunction "PC12_80") (pintype "bidirectional"))
    )
    (net (code "37") (name "/SPI3_SCLK") (class "Default")
      (node (ref "U4") (pin "78") (pinfunction "PC10_78") (pintype "bidirectional"))
    )
    (net (code "38") (name "/SPI3_nCS") (class "Default")
      (node (ref "U4") (pin "77") (pinfunction "PA15_77") (pintype "bidirectional"))
    )
    (net (code "39") (name "/SPI4_MISO") (class "Default")
      (node (ref "U4") (pin "4") (pinfunction "PE5_4") (pintype "bidirectional"))
      (node (ref "U6") (pin "6") (pinfunction "nINT/SDO_6") (pintype "output"))
    )
    (net (code "40") (name "/SPI4_MOSI") (class "Default")
      (node (ref "U4") (pin "5") (pinfunction "PE6_5") (pintype "bidirectional"))
      (node (ref "U6") (pin "11") (pinfunction "SDI_11") (pintype "input"))
    )
    (net (code "41") (name "/SPI4_SCLK") (class "Default")
      (node (ref "U4") (pin "1") (pinfunction "PE2_1") (pintype "bidirectional"))
      (node (ref "U6") (pin "8") (pinfunction "SCLK_8") (pintype "input"))
    )
    (net (code "42") (name "/SPI4_nCS") (class "Default")
      (node (ref "U4") (pin "3") (pinfunction "PE4_3") (pintype "bidirectional"))
      (node (ref "U6") (pin "14") (pinfunction "nCS_14") (pintype "input"))
    )
    (net (code "43") (name "/SWCLK") (class "Default")
      (node (ref "J3") (pin "4") (pinfunction "SWCLK_4") (pintype "input"))
      (node (ref "R82") (pin "2") (pinfunction "2_2") (pintype "passive"))
      (node (ref "U4") (pin "76") (pinfunction "PA14_76") (pintype "bidirectional"))
    )
    (net (code "44") (name "/SWDIO") (class "Default")
      (node (ref "J3") (pin "2") (pinfunction "SWDIO_2") (pintype "input"))
      (node (ref "U4") (pin "72") (pinfunction "PA13_72") (pintype "bidirectional"))
    )
    (net (code "45") (name "/SWO") (class "Default")
      (node (ref "J3") (pin "6") (pinfunction "SWO_6") (pintype "input"))
      (node (ref "U4") (pin "89") (pinfunction "PB3_89") (pintype "bidirectional"))
    )
    (net (code "46") (name "/TRIG_0") (class "Default")
      (node (ref "U4") (pin "38") (pinfunction "PE8_38") (pintype "bidirectional"))
    )
    (net (code "47") (name "/TRIG_1") (class "Default")
      (node (ref "U4") (pin "39") (pinfunction "PE9_39") (pintype "bidirectional"))
    )
    (net (code "48") (name "/TRIG_2") (class "Default")
      (node (ref "U4") (pin "40") (pinfunction "PE10_40") (pintype "bidirectional"))
    )
    (net (code "49") (name "/TRIG_3") (class "Default")
      (node (ref "U4") (pin "41") (pinfunction "PE11_41") (pintype "bidirectional"))
    )
    (net (code "50") (name "/VCC_SENSE") (class "Default")
      (node (ref "U5") (pin "9") (pinfunction "IN5_9") (pintype "input"))
    )
    (net (code "51") (name "/VDDA") (class "Default")
      (node (ref "C29") (pin "1") (pinfunction "1_1") (pintype "passive"))
      (node (ref "C30") (pin "2") (pinfunction "2_2") (pintype "passive"))
      (node (ref "C37") (pin "1") (pinfunction "1_1") (pintype "passive"))
      (node (ref "C38") (pin "2") (pinfunction "2_2") (pintype "passive"))
      (node (ref "FB1") (pin "2") (pinfunction "2_2") (pintype "passive"))
      (node (ref "U4") (pin "20") (pinfunction "VREF+_20") (pintype "power_in"))
      (node (ref "U4") (pin "21") (pinfunction "VDDA_21") (pintype "power_in"))
    )
    (net (code "52") (name "/X32_N") (class "Default")
      (node (ref "C47") (pin "1") (pinfunction "1_1") (pintype "passive"))
      (node (ref "U4") (pin "9") (pinfunction "PC15-OSC32_OUT_9") (pintype "bidirectional"))
      (node (ref "Y2") (pin "2") (pinfunction "Out/In_2") (pintype "passive"))
    )
    (net (code "53") (name "/X32_P") (class "Default")
      (node (ref "C46") (pin "1") (pinfunction "1_1") (pintype "passive"))
      (node (ref "U4") (pin "8") (pinfunction "PC14-OSC32_IN_8") (pintype "bidirectional"))
      (node (ref "Y2") (pin "1") (pinfunction "In/Out_1") (pintype "passive"))
    )
    (net (code "54") (name "/X_N") (class "Default")
      (node (ref "C43") (pin "2") (pinfunction "2_2") (pintype "passive"))
      (node (ref "U4") (pin "13") (pinfunction "PH1-OSC_OUT_13") (pintype "bidirectional"))
      (node (ref "Y1") (pin "1") (pinfunction "1_1") (pintype "passive"))
    )
    (net (code "55") (name "/X_P") (class "Default")
      (node (ref "C42") (pin "2") (pinfunction "2_2") (pintype "passive"))
      (node (ref "U4") (pin "12") (pinfunction "PH0-OSC_IN_12") (pintype "bidirectional"))
      (node (ref "Y1") (pin "3") (pinfunction "3_3") (pintype "passive"))
    )
    (net (code "56") (name "/nWAKE") (class "Default")
      (node (ref "C23") (pin "2") (pinfunction "2_2") (pintype "passive"))
      (node (ref "Q14") (pin "3") (pinfunction "D_3") (pintype "passive"))
      (node (ref "R25") (pin "2") (pinfunction "2_2") (pintype "passive"))
      (node (ref "R27") (pin "2") (pinfunction "2_2") (pintype "passive"))
      (node (ref "SW1") (pin "2") (pinfunction "2_2") (pintype "passive"))
    )
    (net (code "57") (name "3V3") (class "Default")
      (node (ref "C15") (pin "1") (pinfunction "1_1") (pintype "passive"))
      (node (ref "C2") (pin "2") (pinfunction "2_2") (pintype "passive"))
      (node (ref "C20") (pin "2") (pinfunction "2_2") (pintype "passive"))
      (node (ref "C22") (pin "1") (pinfunction "1_1") (pintype "passive"))
      (node (ref "C24") (pin "2") (pinfunction "2_2") (pintype "passive"))
      (node (ref "C26") (pin "2") (pinfunction "2_2") (pintype "passive"))
      (node (ref "C27") (pin "2") (pinfunction "2_2") (pintype "passive"))
      (node (ref "C28") (pin "2") (pinfunction "2_2") (pintype "passive"))
      (node (ref "C35") (pin "1") (pinfunction "1_1") (pintype "passive"))
      (node (ref "C36") (pin "2") (pinfunction "2_2") (pintype "passive"))
      (node (ref "C44") (pin "2") (pinfunction "2_2") (pintype "passive"))
      (node (ref "D10") (pin "2") (pinfunction "A_2") (pintype "passive"))
      (node (ref "D10") (pin "3") (pinfunction "A_3") (pintype "passive"))
      (node (ref "D12") (pin "2") (pinfunction "A_2") (pintype "passive"))
      (node (ref "D12") (pin "3") (pinfunction "A_3") (pintype "passive"))
      (node (ref "FB1") (pin "1") (pinfunction "1_1") (pintype "passive"))
      (node (ref "J3") (pin "1") (pinfunction "VTref_1") (pintype "input"))
      (node (ref "Q12") (pin "3") (pinfunction "D2_3") (pintype "passive"))
      (node (ref "Q12") (pin "6") (pinfunction "D1_6") (pintype "passive"))
      (node (ref "Q13") (pin "3") (pinfunction "D2_3") (pintype "passive"))
      (node (ref "Q13") (pin "6") (pinfunction "D1_6") (pintype "passive"))
      (node (ref "Q15") (pin "3") (pinfunction "D2_3") (pintype "passive"))
      (node (ref "Q15") (pin "6") (pinfunction "D1_6") (pintype "passive"))
      (node (ref "R24") (pin "1") (pinfunction "1_1") (pintype "passive"))
      (node (ref "R35") (pin "2") (pinfunction "2_2") (pintype "passive"))
      (node (ref "R37") (pin "2") (pinfunction "2_2") (pintype "passive"))
      (node (ref "R4") (pin "2") (pinfunction "2_2") (pintype "passive"))
      (node (ref "R48") (pin "1") (pinfunction "1_1") (pintype "passive"))
      (node (ref "R7") (pin "2") (pinfunction "2_2") (pintype "passive"))
      (node (ref "R82") (pin "1") (pinfunction "1_1") (pintype "passive"))
      (node (ref "R84") (pin "2") (pinfunction "2_2") (pintype "passive"))
      (node (ref "R93") (pin "2") (pinfunction "2_2") (pintype "passive"))
      (node (ref "R95") (pin "2") (pinfunction "2_2") (pintype "passive"))
      (node (ref "SW2") (pin "2") (pinfunction "2_2") (pintype "passive"))
      (node (ref "U4") (pin "100") (pinfunction "VDD_100") (pintype "power_in"))
      (node (ref "U4") (pin "11") (pinfunction "VDD_11") (pintype "power_in"))
      (node (ref "U4") (pin "27") (pinfunction "VDD_27") (pintype "power_in"))
      (node (ref "U4") (pin "50") (pinfunction "VDD_50") (pintype "power_in"))
      (node (ref "U4") (pin "6") (pinfunction "VBAT_6") (pintype "power_in"))
      (node (ref "U4") (pin "75") (pinfunction "VDD_75") (pintype "power_in"))
      (node (ref "U5") (pin "2") (pinfunction "VA_2") (pintype "power_in"))
      (node (ref "U6") (pin "5") (pinfunction "VIO_5") (pintype "power_in"))
    )
    (net (code "58") (name "5V") (class "Default")
      (node (ref "C19") (pin "2") (pinfunction "2_2") (pintype "passive"))
      (node (ref "C40") (pin "2") (pinfunction "2_2") (pintype "passive"))
      (node (ref "C48") (pin "1") (pinfunction "1_1") (pintype "passive"))
      (node (ref "R30") (pin "2") (pinfunction "2_2") (pintype "passive"))
      (node (ref "R88") (pin "2") (pinfunction "2_2") (pintype "passive"))
      (node (ref "U1") (pin "2") (pinfunction "VCC_2") (pintype "power_in"))
      (node (ref "U6") (pin "3") (pinfunction "VCC_3") (pintype "power_in"))
      (node (ref "U7") (pin "1") (pinfunction "VOUT_1") (pintype "power_in"))
    )
    (net (code "59") (name "GND") (class "Default")
      (node (ref "C14") (pin "2") (pinfunction "2_2") (pintype "passive"))
      (node (ref "C15") (pin "2") (pinfunction "2_2") (pintype "passive"))
      (node (ref "C16") (pin "2") (pinfunction "2_2") (pintype "passive"))
      (node (ref "C17") (pin "2") (pinfunction "2_2") (pintype "passive"))
      (node (ref "C18") (pin "2") (pinfunction "2_2") (pintype "passive"))
      (node (ref "C19") (pin "1") (pinfunction "1_1") (pintype "passive"))
      (node (ref "C2") (pin "1") (pinfunction "1_1") (pintype "passive"))
      (node (ref "C20") (pin "1") (pinfunction "1_1") (pintype "passive"))
      (node (ref "C21") (pin "1") (pinfunction "1_1") (pintype "passive"))
      (node (ref "C22") (pin "2") (pinfunction "2_2") (pintype "passive"))
      (node (ref "C23") (pin "1") (pinfunction "1_1") (pintype "passive"))
      (node (ref "C24") (pin "1") (pinfunction "1_1") (pintype "passive"))
      (node (ref "C25") (pin "2") (pinfunction "2_2") (pintype "passive"))
      (node (ref "C26") (pin "1") (pinfunction "1_1") (pintype "passive"))
      (node (ref "C27") (pin "1") (pinfunction "1_1") (pintype "passive"))
      (node (ref "C28") (pin "1") (pinfunction "1_1") (pintype "passive"))
      (node (ref "C29") (pin "2") (pinfunction "2_2") (pintype "passive"))
      (node (ref "C30") (pin "1") (pinfunction "1_1") (pintype "passive"))
      (node (ref "C31") (pin "1") (pinfunction "1_1") (pintype "passive"))
      (node (ref "C32") (pin "1") (pinfunction "1_1") (pintype "passive"))
      (node (ref "C33") (pin "1") (pinfunction "1_1") (pintype "passive"))
      (node (ref "C34") (pin "1") (pinfunction "1_1") (pintype "passive"))
      (node (ref "C35") (pin "2") (pinfunction "2_2") (pintype "passive"))
      (node (ref "C36") (pin "1") (pinfunction "1_1") (pintype "passive"))
      (node (ref "C37") (pin "2") (pinfunction "2_2") (pintype "passive"))
      (node (ref "C38") (pin "1") (pinfunction "1_1") (pintype "passive"))
      (node (ref "C39") (pin "1") (pinfunction "1_1") (pintype "passive"))
      (node (ref "C40") (pin "1") (pinfunction "1_1") (pintype "passive"))
      (node (ref "C41") (pin "1") (pinfunction "1_1") (pintype "passive"))
      (node (ref "C42") (pin "1") (pinfunction "1_1") (pintype "passive"))
      (node (ref "C43") (pin "1") (pinfunction "1_1") (pintype "passive"))
      (node (ref "C45") (pin "2") (pinfunction "2_2") (pintype "passive"))
      (node (ref "C46") (pin "2") (pinfunction "2_2") (pintype "passive"))
      (node (ref "C47") (pin "2") (pinfunction "2_2") (pintype "passive"))
      (node (ref "C48") (pin "2") (pinfunction "2_2") (pintype "passive"))
      (node (ref "D8") (pin "3") (pinfunction "3_3") (pintype "passive"))
      (node (ref "J3") (pin "3") (pinfunction "GND_3") (pintype "input"))
      (node (ref "J3") (pin "5") (pinfunction "GND_5") (pintype "input"))
      (node (ref "Q14") (pin "2") (pinfunction "S_2") (pintype "passive"))
      (node (ref "Q3") (pin "1") (pinfunction "Source1_1") (pintype "passive"))
      (node (ref "Q3") (pin "4") (pinfunction "Source2_4") (pintype "passive"))
      (node (ref "R23") (pin "1") (pinfunction "1_1") (pintype "passive"))
      (node (ref "R31") (pin "2") (pinfunction "2_2") (pintype "passive"))
      (node (ref "R33") (pin "1") (pinfunction "1_1") (pintype "passive"))
      (node (ref "R46") (pin "2") (pinfunction "2_2") (pintype "passive"))
      (node (ref "R47") (pin "1") (pinfunction "1_1") (pintype "passive"))
      (node (ref "R8") (pin "1") (pinfunction "1_1") (pintype "passive"))
      (node (ref "R83") (pin "2") (pinfunction "2_2") (pintype "passive"))
      (node (ref "R85") (pin "1") (pinfunction "1_1") (pintype "passive"))
      (node (ref "R87") (pin "1") (pinfunction "1_1") (pintype "passive"))
      (node (ref "R89") (pin "1") (pinfunction "1_1") (pintype "passive"))
      (node (ref "R92") (pin "1") (pinfunction "1_1") (pintype "passive"))
      (node (ref "R96") (pin "1") (pinfunction "1_1") (pintype "passive"))
      (node (ref "R98") (pin "1") (pinfunction "1_1") (pintype "passive"))
      (node (ref "SW1") (pin "1") (pinfunction "1_1") (pintype "passive"))
      (node (ref "SW3") (pin "2") (pinfunction "2_2") (pintype "passive"))
      (node (ref "U1") (pin "11") (pinfunction "GND_11") (pintype "power_in"))
      (node (ref "U4") (pin "10") (pinfunction "VSS_10") (pintype "power_in"))
      (node (ref "U4") (pin "19") (pinfunction "VSSA_19") (pintype "power_in"))
      (node (ref "U4") (pin "26") (pinfunction "VSS_26") (pintype "power_in"))
      (node (ref "U4") (pin "49") (pinfunction "VSS_49") (pintype "power_in"))
      (node (ref "U4") (pin "74") (pinfunction "VSS_74") (pintype "power_in"))
      (node (ref "U4") (pin "99") (pinfunction "VSS_99") (pintype "power_in"))
      (node (ref "U5") (pin "12") (pinfunction "DGND_12") (pintype "power_in"))
      (node (ref "U5") (pin "3") (pinfunction "AGND_3") (pintype "power_in"))
      (node (ref "U6") (pin "2") (pinfunction "GND_2") (pintype "power_in"))
      (node (ref "U7") (pin "2") (pinfunction "GND_2") (pintype "power_in"))
      (node (ref "Y1") (pin "2") (pinfunction "GND_2") (pintype "power_in"))
      (node (ref "Y1") (pin "4") (pinfunction "GND_4") (pintype "power_in"))
    )
    (net (code "60") (name "Net-(C25-Pad1)") (class "Default")
      (node (ref "C25") (pin "1") (pinfunction "1_1") (pintype "passive"))
      (node (ref "R26") (pin "2") (pinfunction "2_2") (pintype "passive"))
      (node (ref "R29") (pin "1") (pinfunction "1_1") (pintype "passive"))
    )
    (net (code "61") (name "Net-(D3-K-Pad1)") (class "Default")
      (node (ref "D3") (pin "1") (pinfunction "K_1") (pintype "passive"))
      (node (ref "R8") (pin "2") (pinfunction "2_2") (pintype "passive"))
    )
    (net (code "62") (name "Net-(D3-K-Pad4)") (class "Default")
      (node (ref "D3") (pin "4") (pinfunction "K_4") (pintype "passive"))
      (node (ref "R33") (pin "2") (pinfunction "2_2") (pintype "passive"))
    )
    (net (code "63") (name "Net-(D7-C)") (class "Default")
      (node (ref "C21") (pin "2") (pinfunction "2_2") (pintype "passive"))
      (node (ref "D7") (pin "1") (pinfunction "C_1") (pintype "passive"))
      (node (ref "R25") (pin "1") (pinfunction "1_1") (pintype "passive"))
      (node (ref "U6") (pin "10") (pinfunction "VSUP_10") (pintype "power_in"))
    )
    (net (code "64") (name "Net-(D9-K-Pad1)") (class "Default")
      (node (ref "D9") (pin "1") (pinfunction "K_1") (pintype "passive"))
      (node (ref "R85") (pin "2") (pinfunction "2_2") (pintype "passive"))
    )
    (net (code "65") (name "Net-(D9-K-Pad4)") (class "Default")
      (node (ref "D9") (pin "4") (pinfunction "K_4") (pintype "passive"))
      (node (ref "R87") (pin "2") (pinfunction "2_2") (pintype "passive"))
    )
    (net (code "66") (name "Net-(D10-K-Pad1)") (class "Default")
      (node (ref "D10") (pin "1") (pinfunction "K_1") (pintype "passive"))
      (node (ref "R38") (pin "2") (pinfunction "2_2") (pintype "passive"))
    )
    (net (code "67") (name "Net-(D10-K-Pad4)") (class "Default")
      (node (ref "D10") (pin "4") (pinfunction "K_4") (pintype "passive"))
      (node (ref "R41") (pin "2") (pinfunction "2_2") (pintype "passive"))
    )
    (net (code "68") (name "Net-(D11-K-Pad1)") (class "Default")
      (node (ref "D11") (pin "1") (pinfunction "K_1") (pintype "passive"))
      (node (ref "R96") (pin "2") (pinfunction "2_2") (pintype "passive"))
    )
    (net (code "69") (name "Net-(D11-K-Pad4)") (class "Default")
      (node (ref "D11") (pin "4") (pinfunction "K_4") (pintype "passive"))
      (node (ref "R98") (pin "2") (pinfunction "2_2") (pintype "passive"))
    )
    (net (code "70") (name "Net-(D12-K-Pad1)") (class "Default")
      (node (ref "D12") (pin "1") (pinfunction "K_1") (pintype "passive"))
      (node (ref "R46") (pin "1") (pinfunction "1_1") (pintype "passive"))
    )
    (net (code "71") (name "Net-(D12-K-Pad4)") (class "Default")
      (node (ref "D12") (pin "4") (pinfunction "K_4") (pintype "passive"))
      (node (ref "R49") (pin "2") (pinfunction "2_2") (pintype "passive"))
    )
    (net (code "72") (name "Net-(Q3A-Gate1)") (class "Default")
      (node (ref "Q3") (pin "2") (pinfunction "Gate1_2") (pintype "passive"))
      (node (ref "Q3") (pin "5") (pinfunction "Gate2_5") (pintype "passive"))
      (node (ref "R37") (pin "1") (pinfunction "1_1") (pintype "passive"))
      (node (ref "R39") (pin "2") (pinfunction "2_2") (pintype "passive"))
    )
    (net (code "73") (name "Net-(Q12A-G1)") (class "Default")
      (node (ref "Q12") (pin "2") (pinfunction "G1_2") (pintype "passive"))
      (node (ref "R4") (pin "1") (pinfunction "1_1") (pintype "passive"))
      (node (ref "R6") (pin "2") (pinfunction "2_2") (pintype "passive"))
    )
    (net (code "74") (name "Net-(Q12A-S1)") (class "Default")
      (node (ref "D3") (pin "2") (pinfunction "A_2") (pintype "passive"))
      (node (ref "Q12") (pin "1") (pinfunction "S1_1") (pintype "passive"))
    )
    (net (code "75") (name "Net-(Q12B-G2)") (class "Default")
      (node (ref "Q12") (pin "5") (pinfunction "G2_5") (pintype "passive"))
      (node (ref "R32") (pin "2") (pinfunction "2_2") (pintype "passive"))
      (node (ref "R7") (pin "1") (pinfunction "1_1") (pintype "passive"))
    )
    (net (code "76") (name "Net-(Q12B-S2)") (class "Default")
      (node (ref "D3") (pin "3") (pinfunction "A_3") (pintype "passive"))
      (node (ref "Q12") (pin "4") (pinfunction "S2_4") (pintype "passive"))
    )
    (net (code "77") (name "Net-(Q13A-G1)") (class "Default")
      (node (ref "Q13") (pin "2") (pinfunction "G1_2") (pintype "passive"))
      (node (ref "R35") (pin "1") (pinfunction "1_1") (pintype "passive"))
      (node (ref "R36") (pin "2") (pinfunction "2_2") (pintype "passive"))
    )
    (net (code "78") (name "Net-(Q13A-S1)") (class "Default")
      (node (ref "D9") (pin "2") (pinfunction "A_2") (pintype "passive"))
      (node (ref "Q13") (pin "1") (pinfunction "S1_1") (pintype "passive"))
    )
    (net (code "79") (name "Net-(Q13B-G2)") (class "Default")
      (node (ref "Q13") (pin "5") (pinfunction "G2_5") (pintype "passive"))
      (node (ref "R84") (pin "1") (pinfunction "1_1") (pintype "passive"))
      (node (ref "R86") (pin "2") (pinfunction "2_2") (pintype "passive"))
    )
    (net (code "80") (name "Net-(Q13B-S2)") (class "Default")
      (node (ref "D9") (pin "3") (pinfunction "A_3") (pintype "passive"))
      (node (ref "Q13") (pin "4") (pinfunction "S2_4") (pintype "passive"))
    )
    (net (code "81") (name "Net-(Q14-G)") (class "Default")
      (node (ref "Q14") (pin "1") (pinfunction "G_1") (pintype "passive"))
      (node (ref "R91") (pin "1") (pinfunction "1_1") (pintype "passive"))
      (node (ref "R92") (pin "2") (pinfunction "2_2") (pintype "passive"))
    )
    (net (code "82") (name "Net-(Q15A-G1)") (class "Default")
      (node (ref "Q15") (pin "2") (pinfunction "G1_2") (pintype "passive"))
      (node (ref "R93") (pin "1") (pinfunction "1_1") (pintype "passive"))
      (node (ref "R94") (pin "2") (pinfunction "2_2") (pintype "passive"))
    )
    (net (code "83") (name "Net-(Q15A-S1)") (class "Default")
      (node (ref "D11") (pin "2") (pinfunction "A_2") (pintype "passive"))
      (node (ref "Q15") (pin "1") (pinfunction "S1_1") (pintype "passive"))
    )
    (net (code "84") (name "Net-(Q15B-G2)") (class "Default")
      (node (ref "Q15") (pin "5") (pinfunction "G2_5") (pintype "passive"))
      (node (ref "R95") (pin "1") (pinfunction "1_1") (pintype "passive"))
      (node (ref "R97") (pin "2") (pinfunction "2_2") (pintype "passive"))
    )
    (net (code "85") (name "Net-(Q15B-S2)") (class "Default")
      (node (ref "D11") (pin "3") (pinfunction "A_3") (pintype "passive"))
      (node (ref "Q15") (pin "4") (pinfunction "S2_4") (pintype "passive"))
    )
    (net (code "86") (name "Net-(R44-Pad2)") (class "Default")
      (node (ref "R44") (pin "2") (pinfunction "2_2") (pintype "passive"))
      (node (ref "SW2") (pin "1") (pinfunction "1_1") (pintype "passive"))
    )
    (net (code "87") (name "Net-(R45-Pad2)") (class "Default")
      (node (ref "R45") (pin "2") (pinfunction "2_2") (pintype "passive"))
      (node (ref "SW3") (pin "1") (pinfunction "1_1") (pintype "passive"))
    )
    (net (code "88") (name "Net-(TP3-TP)") (class "Default")
      (node (ref "C31") (pin "2") (pinfunction "2_2") (pintype "passive"))
      (node (ref "C32") (pin "2") (pinfunction "2_2") (pintype "passive"))
      (node (ref "TP3") (pin "1") (pinfunction "TP_1") (pintype "passive"))
      (node (ref "U4") (pin "48") (pinfunction "VCAP_48") (pintype "power_in"))
    )
    (net (code "89") (name "Net-(TP8-TP)") (class "Default")
      (node (ref "C33") (pin "2") (pinfunction "2_2") (pintype "passive"))
      (node (ref "C34") (pin "2") (pinfunction "2_2") (pintype "passive"))
      (node (ref "TP8") (pin "1") (pinfunction "TP_1") (pintype "passive"))
      (node (ref "U4") (pin "73") (pinfunction "VCAP_73") (pintype "power_in"))
    )
    (net (code "90") (name "Net-(U1A-1IN-)") (class "Default")
      (node (ref "R88") (pin "1") (pinfunction "1_1") (pintype "passive"))
      (node (ref "R89") (pin "2") (pinfunction "2_2") (pintype "passive"))
      (node (ref "U1") (pin "16") (pinfunction "1IN-_16") (pintype "input"))
    )
    (net (code "91") (name "Net-(U1A-1OUT)") (class "Default")
      (node (ref "R91") (pin "2") (pinfunction "2_2") (pintype "passive"))
      (node (ref "U1") (pin "15") (pinfunction "1OUT_15") (pintype "output"))
    )
    (net (code "92") (name "Net-(U1B-2IN+)") (class "Default")
      (node (ref "R90") (pin "2") (pinfunction "2_2") (pintype "passive"))
      (node (ref "U1") (pin "4") (pinfunction "2IN+_4") (pintype "input"))
    )
    (net (code "93") (name "Net-(U1C-3IN+)") (class "Default")
      (node (ref "R43") (pin "2") (pinfunction "2_2") (pintype "passive"))
      (node (ref "R83") (pin "1") (pinfunction "1_1") (pintype "passive"))
      (node (ref "U1") (pin "9") (pinfunction "3IN+_9") (pintype "input"))
    )
    (net (code "94") (name "Net-(U1C-3IN-)") (class "Default")
      (node (ref "R34") (pin "1") (pinfunction "1_1") (pintype "passive"))
      (node (ref "R42") (pin "2") (pinfunction "2_2") (pintype "passive"))
      (node (ref "U1") (pin "8") (pinfunction "3IN-_8") (pintype "input"))
    )
    (net (code "95") (name "Net-(U1D-4IN+)") (class "Default")
      (node (ref "R40") (pin "2") (pinfunction "2_2") (pintype "passive"))
      (node (ref "U1") (pin "12") (pinfunction "4IN+_12") (pintype "input"))
    )
    (net (code "96") (name "Net-(U4B-BOOT0)") (class "Default")
      (node (ref "R22") (pin "1") (pinfunction "1_1") (pintype "passive"))
      (node (ref "R23") (pin "2") (pinfunction "2_2") (pintype "passive"))
      (node (ref "U4") (pin "94") (pinfunction "BOOT0_94") (pintype "input"))
    )
    (net (code "97") (name "Net-(U4B-~{RST})") (class "Default")
      (node (ref "C14") (pin "1") (pinfunction "1_1") (pintype "passive"))
      (node (ref "R21") (pin "1") (pinfunction "1_1") (pintype "passive"))
      (node (ref "U4") (pin "14") (pinfunction "~{RST}_14") (pintype "input"))
    )
    (net (code "98") (name "Net-(U5-VD)") (class "Default")
      (node (ref "C16") (pin "1") (pinfunction "1_1") (pintype "passive"))
      (node (ref "C17") (pin "1") (pinfunction "1_1") (pintype "passive"))
      (node (ref "R24") (pin "2") (pinfunction "2_2") (pintype "passive"))
      (node (ref "U5") (pin "13") (pinfunction "VD_13") (pintype "power_in"))
    )
    (net (code "99") (name "Net-(U6-WAKE)") (class "Default")
      (node (ref "R27") (pin "1") (pinfunction "1_1") (pintype "passive"))
      (node (ref "U6") (pin "9") (pinfunction "WAKE_9") (pintype "input"))
    )
    (net (code "100") (name "VCC") (class "Default")
      (node (ref "C41") (pin "2") (pinfunction "2_2") (pintype "passive"))
      (node (ref "LS1") (pin "P") (pinfunction "P_P") (pintype "passive"))
      (node (ref "U7") (pin "3") (pinfunction "VIN_3") (pintype "power_in"))
    )
    (net (code "101") (name "unconnected-(J3-NC-Pad7)") (class "Default")
      (node (ref "J3") (pin "7") (pinfunction "NC_7") (pintype "input+no_connect"))
    )
    (net (code "102") (name "unconnected-(J3-NC-Pad9)") (class "Default")
      (node (ref "J3") (pin "9") (pinfunction "NC_9") (pintype "input+no_connect"))
    )
    (net (code "103") (name "unconnected-(J3-TDI-Pad8)") (class "Default")
      (node (ref "J3") (pin "8") (pinfunction "TDI_8") (pintype "input+no_connect"))
    )
    (net (code "104") (name "unconnected-(U4B-PA0-Pad22)") (class "Default")
      (node (ref "U4") (pin "22") (pinfunction "PA0_22") (pintype "bidirectional"))
    )
    (net (code "105") (name "unconnected-(U4B-PA1-Pad23)") (class "Default")
      (node (ref "U4") (pin "23") (pinfunction "PA1_23") (pintype "bidirectional"))
    )
    (net (code "106") (name "unconnected-(U4B-PA2-Pad24)") (class "Default")
      (node (ref "U4") (pin "24") (pinfunction "PA2_24") (pintype "bidirectional"))
    )
    (net (code "107") (name "unconnected-(U4B-PA8-Pad67)") (class "Default")
      (node (ref "U4") (pin "67") (pinfunction "PA8_67") (pintype "bidirectional"))
    )
    (net (code "108") (name "unconnected-(U4B-PA9-Pad68)") (class "Default")
      (node (ref "U4") (pin "68") (pinfunction "PA9_68") (pintype "bidirectional"))
    )
    (net (code "109") (name "unconnected-(U4B-PA10-Pad69)") (class "Default")
      (node (ref "U4") (pin "69") (pinfunction "PA10_69") (pintype "bidirectional"))
    )
    (net (code "110") (name "unconnected-(U4B-PA11-Pad70)") (class "Default")
      (node (ref "U4") (pin "70") (pinfunction "PA11_70") (pintype "bidirectional"))
    )
    (net (code "111") (name "unconnected-(U4B-PA12-Pad71)") (class "Default")
      (node (ref "U4") (pin "71") (pinfunction "PA12_71") (pintype "bidirectional"))
    )
    (net (code "112") (name "unconnected-(U4B-PB0-Pad34)") (class "Default")
      (node (ref "U4") (pin "34") (pinfunction "PB0_34") (pintype "bidirectional"))
    )
    (net (code "113") (name "unconnected-(U4B-PB1-Pad35)") (class "Default")
      (node (ref "U4") (pin "35") (pinfunction "PB1_35") (pintype "bidirectional"))
    )
    (net (code "114") (name "unconnected-(U4B-PB2-Pad36)") (class "Default")
      (node (ref "U4") (pin "36") (pinfunction "PB2_36") (pintype "bidirectional"))
    )
    (net (code "115") (name "unconnected-(U4B-PB4-Pad90)") (class "Default")
      (node (ref "U4") (pin "90") (pinfunction "PB4_90") (pintype "bidirectional"))
    )
    (net (code "116") (name "unconnected-(U4B-PB5-Pad91)") (class "Default")
      (node (ref "U4") (pin "91") (pinfunction "PB5_91") (pintype "bidirectional"))
    )
    (net (code "117") (name "unconnected-(U4B-PB6-Pad92)") (class "Default")
      (node (ref "U4") (pin "92") (pinfunction "PB6_92") (pintype "bidirectional"))
    )
    (net (code "118") (name "unconnected-(U4B-PB7-Pad93)") (class "Default")
      (node (ref "U4") (pin "93") (pinfunction "PB7_93") (pintype "bidirectional"))
    )
    (net (code "119") (name "unconnected-(U4B-PB10-Pad46)") (class "Default")
      (node (ref "U4") (pin "46") (pinfunction "PB10_46") (pintype "bidirectional"))
    )
    (net (code "120") (name "unconnected-(U4B-PB11-Pad47)") (class "Default")
      (node (ref "U4") (pin "47") (pinfunction "PB11_47") (pintype "bidirectional"))
    )
    (net (code "121") (name "unconnected-(U4B-PC2_C-Pad17)") (class "Default")
      (node (ref "U4") (pin "17") (pinfunction "PC2_C_17") (pintype "bidirectional"))
    )
    (net (code "122") (name "unconnected-(U4B-PC3_C-Pad18)") (class "Default")
      (node (ref "U4") (pin "18") (pinfunction "PC3_C_18") (pintype "bidirectional"))
    )
    (net (code "123") (name "unconnected-(U4B-PC4-Pad32)") (class "Default")
      (node (ref "U4") (pin "32") (pinfunction "PC4_32") (pintype "bidirectional"))
    )
    (net (code "124") (name "unconnected-(U4B-PC5-Pad33)") (class "Default")
      (node (ref "U4") (pin "33") (pinfunction "PC5_33") (pintype "bidirectional"))
    )
    (net (code "125") (name "unconnected-(U4B-PC6-Pad63)") (class "Default")
      (node (ref "U4") (pin "63") (pinfunction "PC6_63") (pintype "bidirectional"))
    )
    (net (code "126") (name "unconnected-(U4B-PC7-Pad64)") (class "Default")
      (node (ref "U4") (pin "64") (pinfunction "PC7_64") (pintype "bidirectional"))
    )
    (net (code "127") (name "unconnected-(U4B-PC8-Pad65)") (class "Default")
      (node (ref "U4") (pin "65") (pinfunction "PC8_65") (pintype "bidirectional"))
    )
    (net (code "128") (name "unconnected-(U4B-PC9-Pad66)") (class "Default")
      (node (ref "U4") (pin "66") (pinfunction "PC9_66") (pintype "bidirectional"))
    )
    (net (code "129") (name "unconnected-(U4B-PC13-Pad7)") (class "Default")
      (node (ref "U4") (pin "7") (pinfunction "PC13_7") (pintype "bidirectional"))
    )
    (net (code "130") (name "unconnected-(U4B-PD0-Pad81)") (class "Default")
      (node (ref "U4") (pin "81") (pinfunction "PD0_81") (pintype "bidirectional"))
    )
    (net (code "131") (name "unconnected-(U4B-PD1-Pad82)") (class "Default")
      (node (ref "U4") (pin "82") (pinfunction "PD1_82") (pintype "bidirectional"))
    )
    (net (code "132") (name "unconnected-(U4B-PD2-Pad83)") (class "Default")
      (node (ref "U4") (pin "83") (pinfunction "PD2_83") (pintype "bidirectional"))
    )
    (net (code "133") (name "unconnected-(U4B-PD3-Pad84)") (class "Default")
      (node (ref "U4") (pin "84") (pinfunction "PD3_84") (pintype "bidirectional"))
    )
    (net (code "134") (name "unconnected-(U4B-PD4-Pad85)") (class "Default")
      (node (ref "U4") (pin "85") (pinfunction "PD4_85") (pintype "bidirectional"))
    )
    (net (code "135") (name "unconnected-(U4B-PD5-Pad86)") (class "Default")
      (node (ref "U4") (pin "86") (pinfunction "PD5_86") (pintype "bidirectional"))
    )
    (net (code "136") (name "unconnected-(U4B-PD6-Pad87)") (class "Default")
      (node (ref "U4") (pin "87") (pinfunction "PD6_87") (pintype "bidirectional"))
    )
    (net (code "137") (name "unconnected-(U4B-PD7-Pad88)") (class "Default")
      (node (ref "U4") (pin "88") (pinfunction "PD7_88") (pintype "bidirectional"))
    )
    (net (code "138") (name "unconnected-(U4B-PD8-Pad55)") (class "Default")
      (node (ref "U4") (pin "55") (pinfunction "PD8_55") (pintype "bidirectional"))
    )
    (net (code "139") (name "unconnected-(U4B-PD9-Pad56)") (class "Default")
      (node (ref "U4") (pin "56") (pinfunction "PD9_56") (pintype "bidirectional"))
    )
    (net (code "140") (name "unconnected-(U4B-PD10-Pad57)") (class "Default")
      (node (ref "U4") (pin "57") (pinfunction "PD10_57") (pintype "bidirectional"))
    )
    (net (code "141") (name "unconnected-(U4B-PD11-Pad58)") (class "Default")
      (node (ref "U4") (pin "58") (pinfunction "PD11_58") (pintype "bidirectional"))
    )
    (net (code "142") (name "unconnected-(U4B-PD14-Pad61)") (class "Default")
      (node (ref "U4") (pin "61") (pinfunction "PD14_61") (pintype "bidirectional"))
    )
    (net (code "143") (name "unconnected-(U4B-PD15-Pad62)") (class "Default")
      (node (ref "U4") (pin "62") (pinfunction "PD15_62") (pintype "bidirectional"))
    )
    (net (code "144") (name "unconnected-(U4B-PE0-Pad97)") (class "Default")
      (node (ref "U4") (pin "97") (pinfunction "PE0_97") (pintype "bidirectional"))
    )
    (net (code "145") (name "unconnected-(U4B-PE1-Pad98)") (class "Default")
      (node (ref "U4") (pin "98") (pinfunction "PE1_98") (pintype "bidirectional"))
    )
    (net (code "146") (name "unconnected-(U4B-PE3-Pad2)") (class "Default")
      (node (ref "U4") (pin "2") (pinfunction "PE3_2") (pintype "bidirectional"))
    )
    (net (code "147") (name "unconnected-(U4B-PE7-Pad37)") (class "Default")
      (node (ref "U4") (pin "37") (pinfunction "PE7_37") (pintype "bidirectional"))
    )
    (net (code "148") (name "unconnected-(U4B-PE12-Pad42)") (class "Default")
      (node (ref "U4") (pin "42") (pinfunction "PE12_42") (pintype "bidirectional"))
    )
    (net (code "149") (name "unconnected-(U4B-PE13-Pad43)") (class "Default")
      (node (ref "U4") (pin "43") (pinfunction "PE13_43") (pintype "bidirectional"))
    )
    (net (code "150") (name "unconnected-(U4B-PE14-Pad44)") (class "Default")
      (node (ref "U4") (pin "44") (pinfunction "PE14_44") (pintype "bidirectional"))
    )
    (net (code "151") (name "unconnected-(U4B-PE15-Pad45)") (class "Default")
      (node (ref "U4") (pin "45") (pinfunction "PE15_45") (pintype "bidirectional"))
    )
  )
)
